# altair.net
KiCad netlist of a schematic drawn in EAGLE
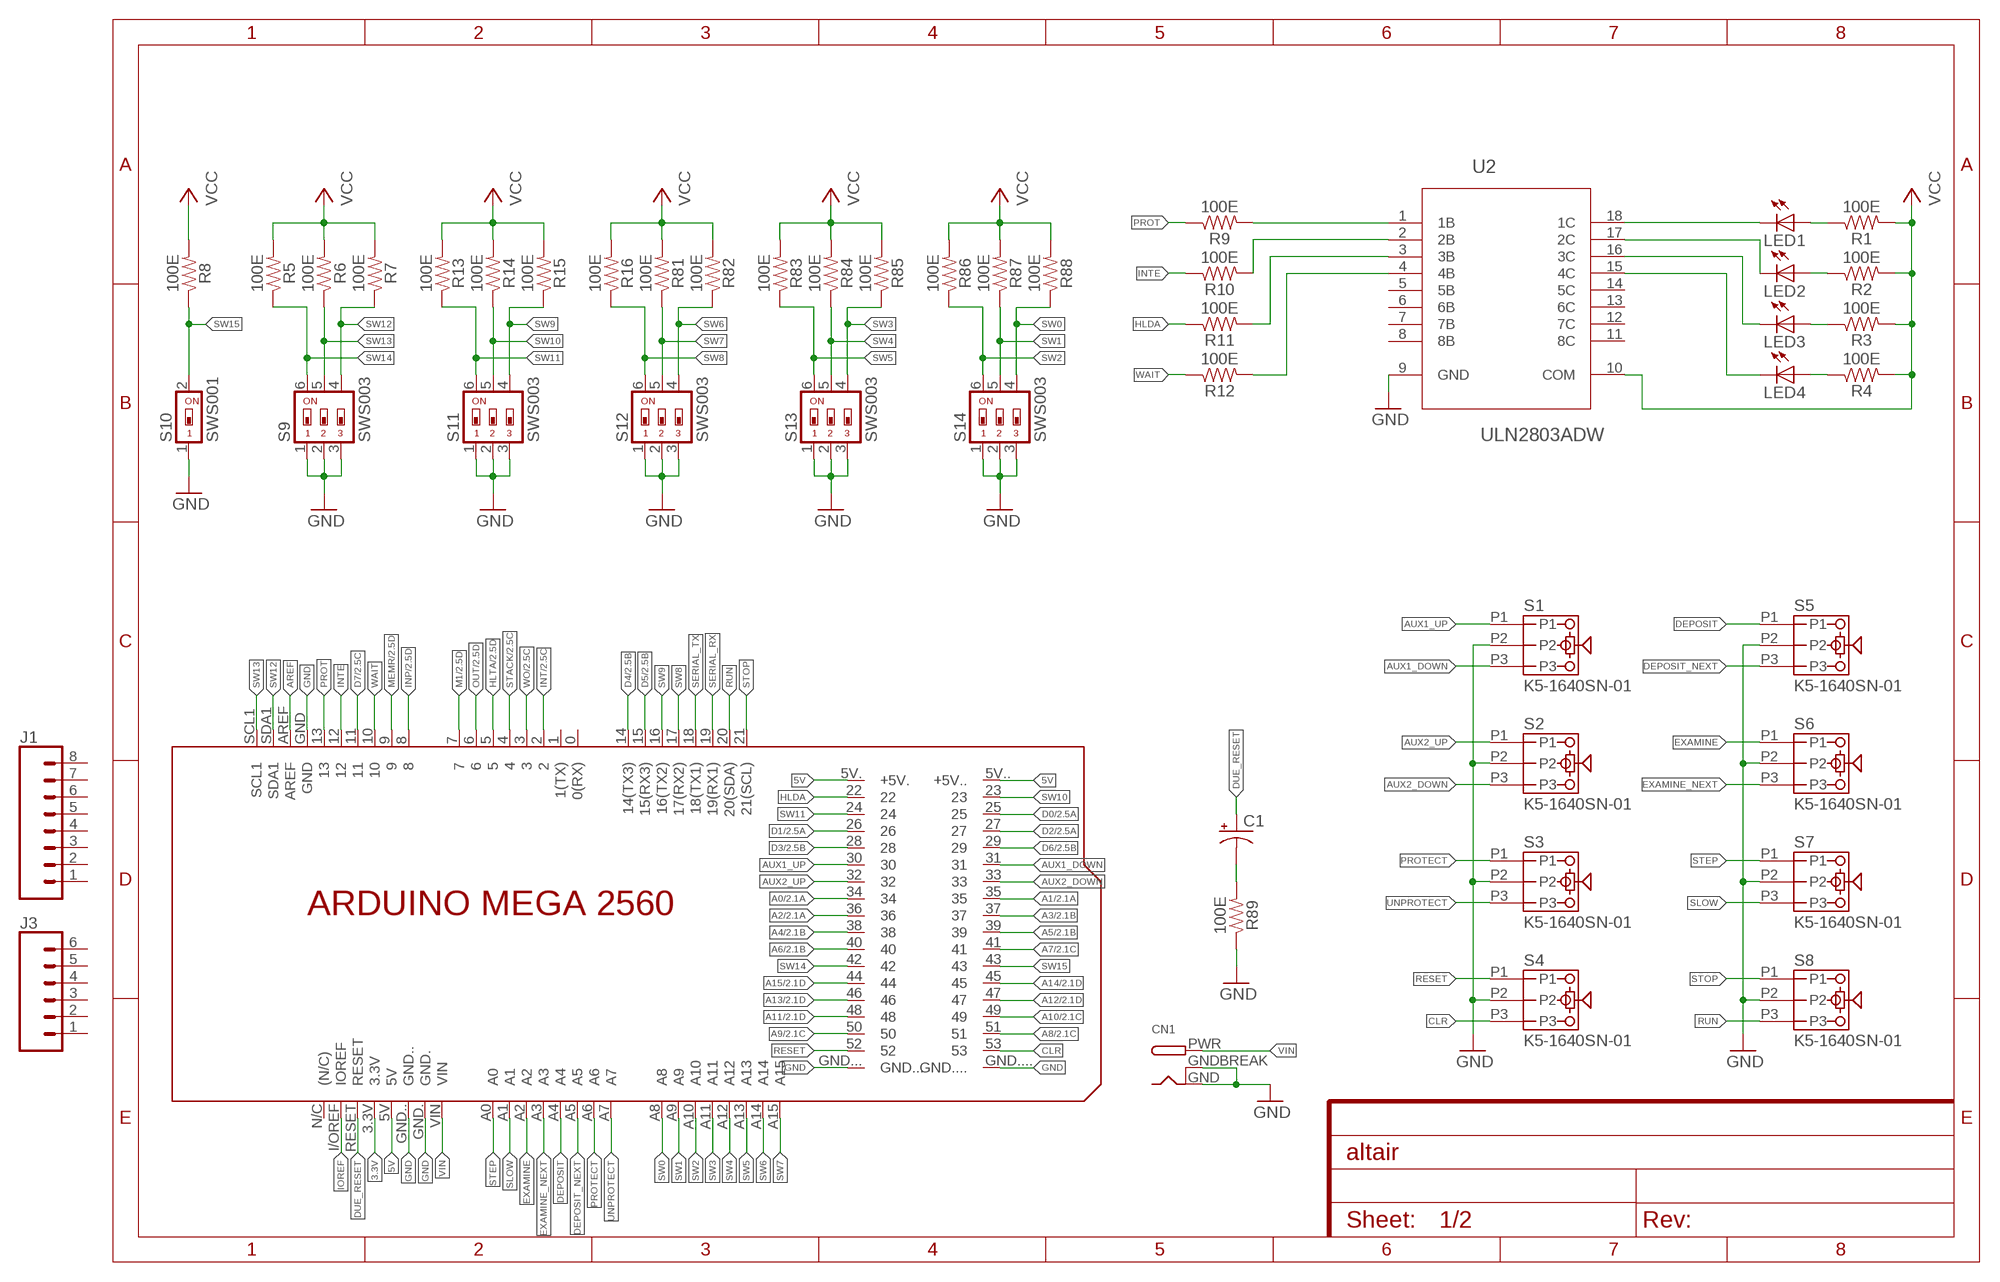
[diagram p0: schematic, sheet 1]
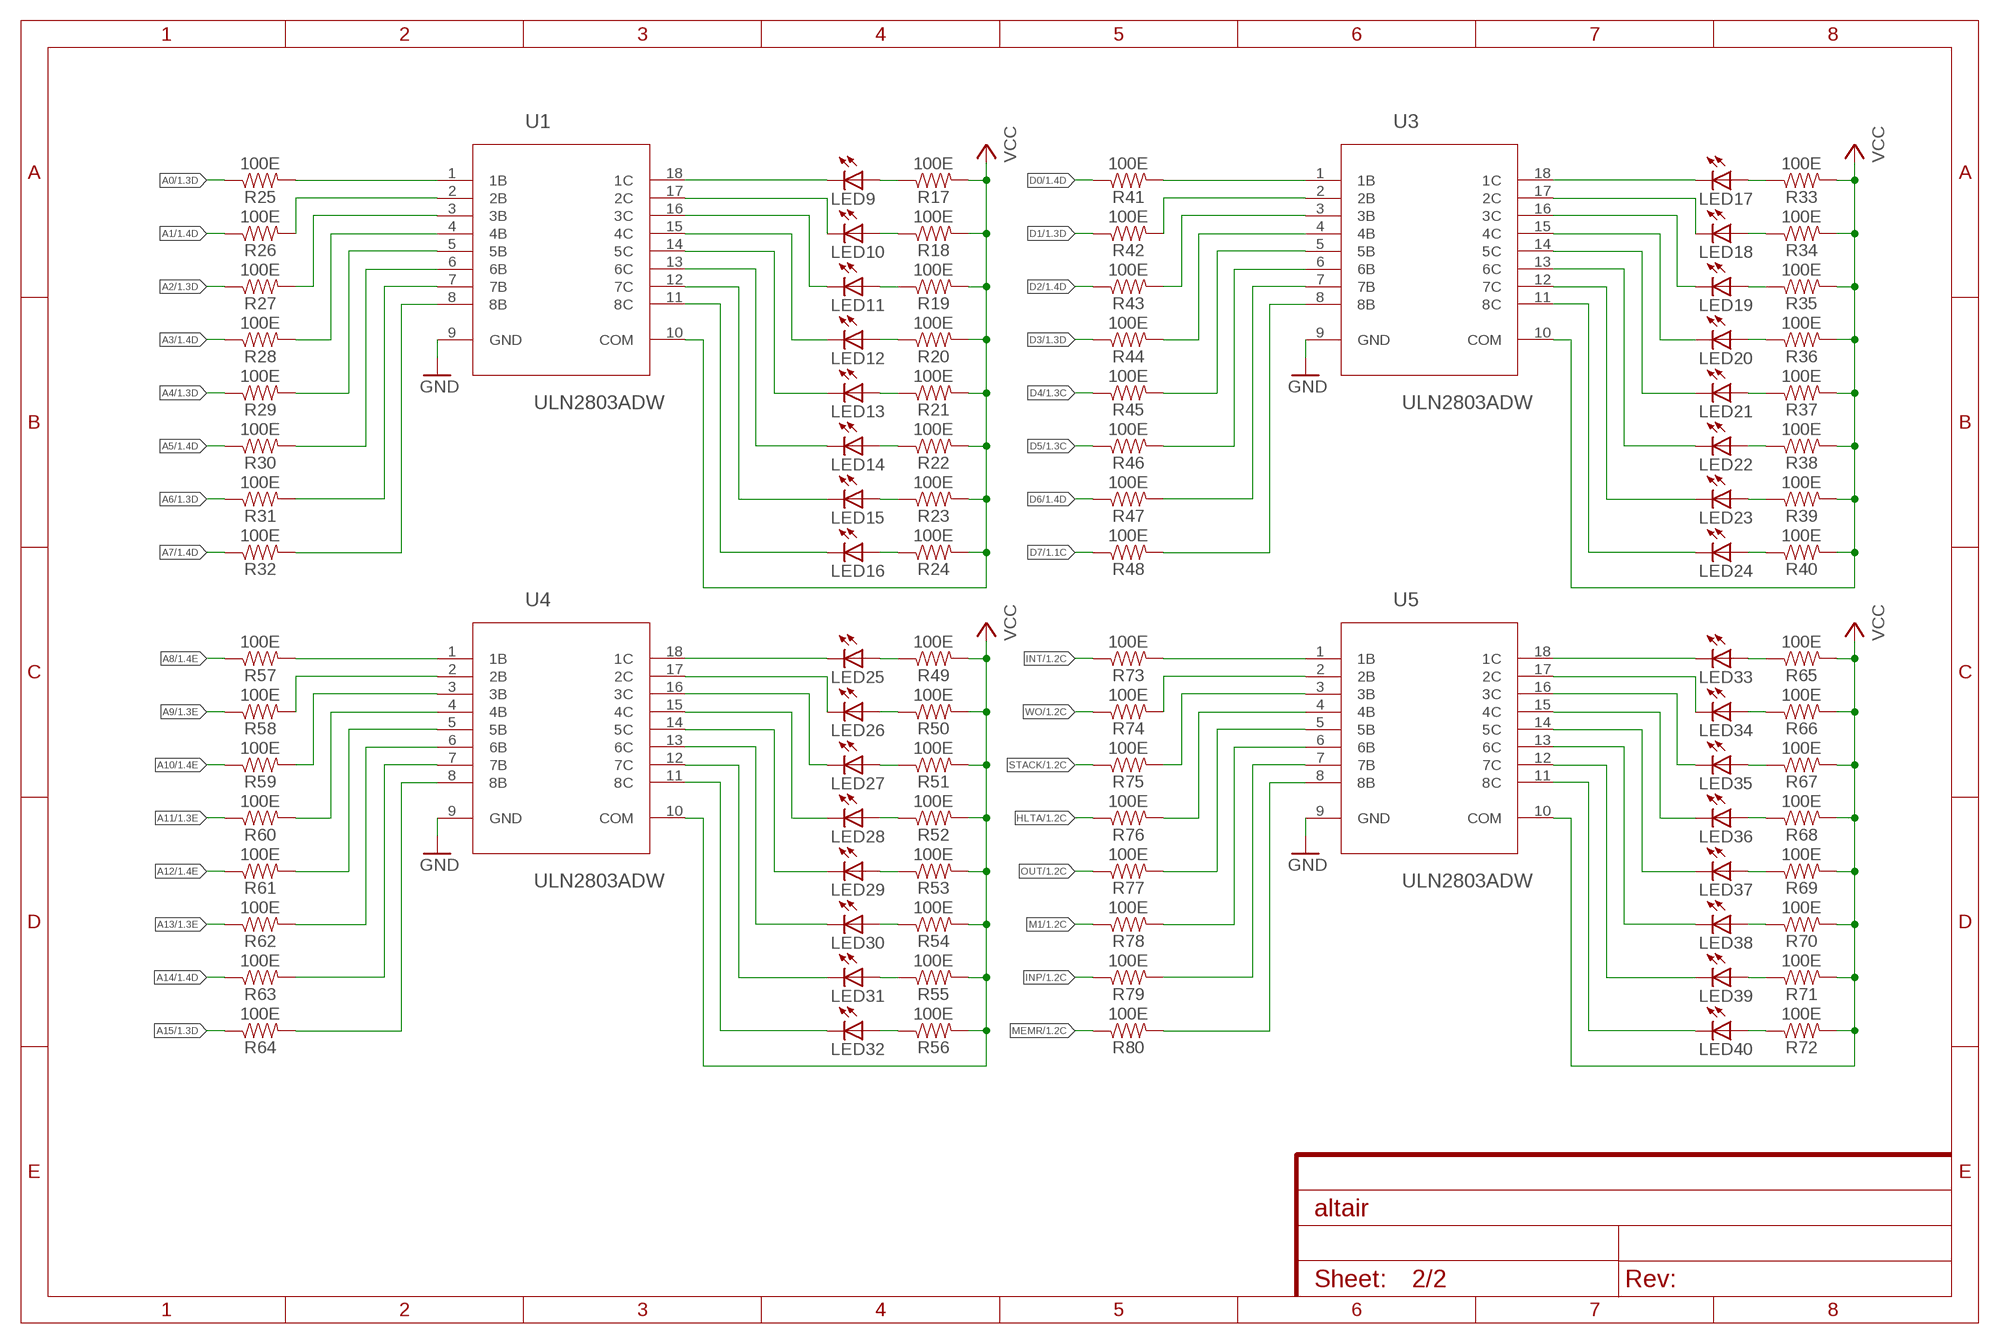
[diagram p1: schematic, sheet 2]

(export (version "E")
  (design (tool "Eeschema 10.0.6"))
  (components
    (comp (ref "C1")
      (value "CPOL-USD")
      (footprint "eagle-import:PANASONIC_D")
      (libsource (lib "eagle-import") (part "CPOL-USD"))
    )
    (comp (ref "CN1")
      (value "DCBARRELPTH")
      (footprint "eagle-import:DCJACK_2MM_PTH")
      (libsource (lib "eagle-import") (part "DCBARRELPTH"))
    )
    (comp (ref "J1")
      (value "CONN_08LOCK")
      (footprint "eagle-import:1X08_LOCK")
      (libsource (lib "eagle-import") (part "CONN_08LOCK"))
    )
    (comp (ref "J3")
      (value "CONN_06LOCK")
      (footprint "eagle-import:1X06_LOCK")
      (libsource (lib "eagle-import") (part "CONN_06LOCK"))
    )
    (comp (ref "LED1")
      (value "LEDCHIP-LED0805")
      (footprint "eagle-import:CHIP-LED0805")
      (libsource (lib "eagle-import") (part "LEDCHIP-LED0805"))
    )
    (comp (ref "LED2")
      (value "LEDCHIP-LED0805")
      (footprint "eagle-import:CHIP-LED0805")
      (libsource (lib "eagle-import") (part "LEDCHIP-LED0805"))
    )
    (comp (ref "LED3")
      (value "LEDCHIP-LED0805")
      (footprint "eagle-import:CHIP-LED0805")
      (libsource (lib "eagle-import") (part "LEDCHIP-LED0805"))
    )
    (comp (ref "LED4")
      (value "LEDCHIP-LED0805")
      (footprint "eagle-import:CHIP-LED0805")
      (libsource (lib "eagle-import") (part "LEDCHIP-LED0805"))
    )
    (comp (ref "PCB2")
      (value "ARDUINO_MEGA2560")
      (footprint "eagle-import:ARDUINO_MEGA2560")
      (libsource (lib "eagle-import") (part "ARDUINO_MEGA2560"))
    )
    (comp (ref "R1")
      (value "100E")
      (footprint "eagle-import:0805")
      (libsource (lib "eagle-import") (part "RESISTOR0805"))
    )
    (comp (ref "R2")
      (value "100E")
      (footprint "eagle-import:0805")
      (libsource (lib "eagle-import") (part "RESISTOR0805"))
    )
    (comp (ref "R3")
      (value "100E")
      (footprint "eagle-import:0805")
      (libsource (lib "eagle-import") (part "RESISTOR0805"))
    )
    (comp (ref "R4")
      (value "100E")
      (footprint "eagle-import:0805")
      (libsource (lib "eagle-import") (part "RESISTOR0805"))
    )
    (comp (ref "R5")
      (value "100E")
      (footprint "eagle-import:0805")
      (libsource (lib "eagle-import") (part "RESISTOR0805"))
    )
    (comp (ref "R6")
      (value "100E")
      (footprint "eagle-import:0805")
      (libsource (lib "eagle-import") (part "RESISTOR0805"))
    )
    (comp (ref "R7")
      (value "100E")
      (footprint "eagle-import:0805")
      (libsource (lib "eagle-import") (part "RESISTOR0805"))
    )
    (comp (ref "R8")
      (value "100E")
      (footprint "eagle-import:0805")
      (libsource (lib "eagle-import") (part "RESISTOR0805"))
    )
    (comp (ref "R9")
      (value "100E")
      (footprint "eagle-import:0805")
      (libsource (lib "eagle-import") (part "RESISTOR0805"))
    )
    (comp (ref "R10")
      (value "100E")
      (footprint "eagle-import:0805")
      (libsource (lib "eagle-import") (part "RESISTOR0805"))
    )
    (comp (ref "R11")
      (value "100E")
      (footprint "eagle-import:0805")
      (libsource (lib "eagle-import") (part "RESISTOR0805"))
    )
    (comp (ref "R12")
      (value "100E")
      (footprint "eagle-import:0805")
      (libsource (lib "eagle-import") (part "RESISTOR0805"))
    )
    (comp (ref "R13")
      (value "100E")
      (footprint "eagle-import:0805")
      (libsource (lib "eagle-import") (part "RESISTOR0805"))
    )
    (comp (ref "R14")
      (value "100E")
      (footprint "eagle-import:0805")
      (libsource (lib "eagle-import") (part "RESISTOR0805"))
    )
    (comp (ref "R15")
      (value "100E")
      (footprint "eagle-import:0805")
      (libsource (lib "eagle-import") (part "RESISTOR0805"))
    )
    (comp (ref "R16")
      (value "100E")
      (footprint "eagle-import:0805")
      (libsource (lib "eagle-import") (part "RESISTOR0805"))
    )
    (comp (ref "R81")
      (value "100E")
      (footprint "eagle-import:0805")
      (libsource (lib "eagle-import") (part "RESISTOR0805"))
    )
    (comp (ref "R82")
      (value "100E")
      (footprint "eagle-import:0805")
      (libsource (lib "eagle-import") (part "RESISTOR0805"))
    )
    (comp (ref "R83")
      (value "100E")
      (footprint "eagle-import:0805")
      (libsource (lib "eagle-import") (part "RESISTOR0805"))
    )
    (comp (ref "R84")
      (value "100E")
      (footprint "eagle-import:0805")
      (libsource (lib "eagle-import") (part "RESISTOR0805"))
    )
    (comp (ref "R85")
      (value "100E")
      (footprint "eagle-import:0805")
      (libsource (lib "eagle-import") (part "RESISTOR0805"))
    )
    (comp (ref "R86")
      (value "100E")
      (footprint "eagle-import:0805")
      (libsource (lib "eagle-import") (part "RESISTOR0805"))
    )
    (comp (ref "R87")
      (value "100E")
      (footprint "eagle-import:0805")
      (libsource (lib "eagle-import") (part "RESISTOR0805"))
    )
    (comp (ref "R88")
      (value "100E")
      (footprint "eagle-import:0805")
      (libsource (lib "eagle-import") (part "RESISTOR0805"))
    )
    (comp (ref "R89")
      (value "100E")
      (footprint "eagle-import:0805")
      (libsource (lib "eagle-import") (part "RESISTOR0805"))
    )
    (comp (ref "S1")
      (value "K5-1640SN-01")
      (footprint "eagle-import:K5-1640SN-01")
      (libsource (lib "eagle-import") (part "K5-1640SN-01"))
    )
    (comp (ref "S2")
      (value "K5-1640SN-01")
      (footprint "eagle-import:K5-1640SN-01")
      (libsource (lib "eagle-import") (part "K5-1640SN-01"))
    )
    (comp (ref "S3")
      (value "K5-1640SN-01")
      (footprint "eagle-import:K5-1640SN-01")
      (libsource (lib "eagle-import") (part "K5-1640SN-01"))
    )
    (comp (ref "S4")
      (value "K5-1640SN-01")
      (footprint "eagle-import:K5-1640SN-01")
      (libsource (lib "eagle-import") (part "K5-1640SN-01"))
    )
    (comp (ref "S5")
      (value "K5-1640SN-01")
      (footprint "eagle-import:K5-1640SN-01")
      (libsource (lib "eagle-import") (part "K5-1640SN-01"))
    )
    (comp (ref "S6")
      (value "K5-1640SN-01")
      (footprint "eagle-import:K5-1640SN-01")
      (libsource (lib "eagle-import") (part "K5-1640SN-01"))
    )
    (comp (ref "S7")
      (value "K5-1640SN-01")
      (footprint "eagle-import:K5-1640SN-01")
      (libsource (lib "eagle-import") (part "K5-1640SN-01"))
    )
    (comp (ref "S8")
      (value "K5-1640SN-01")
      (footprint "eagle-import:K5-1640SN-01")
      (libsource (lib "eagle-import") (part "K5-1640SN-01"))
    )
    (comp (ref "S9")
      (value "SWS003")
      (footprint "eagle-import:SMS-003")
      (libsource (lib "eagle-import") (part "SWS003"))
    )
    (comp (ref "S10")
      (value "SWS001")
      (footprint "eagle-import:SMS-001")
      (libsource (lib "eagle-import") (part "SWS001"))
    )
    (comp (ref "S11")
      (value "SWS003")
      (footprint "eagle-import:SMS-003")
      (libsource (lib "eagle-import") (part "SWS003"))
    )
    (comp (ref "S12")
      (value "SWS003")
      (footprint "eagle-import:SMS-003")
      (libsource (lib "eagle-import") (part "SWS003"))
    )
    (comp (ref "S13")
      (value "SWS003")
      (footprint "eagle-import:SMS-003")
      (libsource (lib "eagle-import") (part "SWS003"))
    )
    (comp (ref "S14")
      (value "SWS003")
      (footprint "eagle-import:SMS-003")
      (libsource (lib "eagle-import") (part "SWS003"))
    )
    (comp (ref "U2")
      (value "ULN2803ADW")
      (footprint "eagle-import:SOIC127P1030X265-18N")
      (libsource (lib "eagle-import") (part "ULN2803ADW"))
    )
    (comp (ref "LED9")
      (value "LEDCHIP-LED0805")
      (footprint "eagle-import:CHIP-LED0805")
      (libsource (lib "eagle-import") (part "LEDCHIP-LED0805"))
    )
    (comp (ref "LED10")
      (value "LEDCHIP-LED0805")
      (footprint "eagle-import:CHIP-LED0805")
      (libsource (lib "eagle-import") (part "LEDCHIP-LED0805"))
    )
    (comp (ref "LED11")
      (value "LEDCHIP-LED0805")
      (footprint "eagle-import:CHIP-LED0805")
      (libsource (lib "eagle-import") (part "LEDCHIP-LED0805"))
    )
    (comp (ref "LED12")
      (value "LEDCHIP-LED0805")
      (footprint "eagle-import:CHIP-LED0805")
      (libsource (lib "eagle-import") (part "LEDCHIP-LED0805"))
    )
    (comp (ref "LED13")
      (value "LEDCHIP-LED0805")
      (footprint "eagle-import:CHIP-LED0805")
      (libsource (lib "eagle-import") (part "LEDCHIP-LED0805"))
    )
    (comp (ref "LED14")
      (value "LEDCHIP-LED0805")
      (footprint "eagle-import:CHIP-LED0805")
      (libsource (lib "eagle-import") (part "LEDCHIP-LED0805"))
    )
    (comp (ref "LED15")
      (value "LEDCHIP-LED0805")
      (footprint "eagle-import:CHIP-LED0805")
      (libsource (lib "eagle-import") (part "LEDCHIP-LED0805"))
    )
    (comp (ref "LED16")
      (value "LEDCHIP-LED0805")
      (footprint "eagle-import:CHIP-LED0805")
      (libsource (lib "eagle-import") (part "LEDCHIP-LED0805"))
    )
    (comp (ref "LED17")
      (value "LEDCHIP-LED0805")
      (footprint "eagle-import:CHIP-LED0805")
      (libsource (lib "eagle-import") (part "LEDCHIP-LED0805"))
    )
    (comp (ref "LED18")
      (value "LEDCHIP-LED0805")
      (footprint "eagle-import:CHIP-LED0805")
      (libsource (lib "eagle-import") (part "LEDCHIP-LED0805"))
    )
    (comp (ref "LED19")
      (value "LEDCHIP-LED0805")
      (footprint "eagle-import:CHIP-LED0805")
      (libsource (lib "eagle-import") (part "LEDCHIP-LED0805"))
    )
    (comp (ref "LED20")
      (value "LEDCHIP-LED0805")
      (footprint "eagle-import:CHIP-LED0805")
      (libsource (lib "eagle-import") (part "LEDCHIP-LED0805"))
    )
    (comp (ref "LED21")
      (value "LEDCHIP-LED0805")
      (footprint "eagle-import:CHIP-LED0805")
      (libsource (lib "eagle-import") (part "LEDCHIP-LED0805"))
    )
    (comp (ref "LED22")
      (value "LEDCHIP-LED0805")
      (footprint "eagle-import:CHIP-LED0805")
      (libsource (lib "eagle-import") (part "LEDCHIP-LED0805"))
    )
    (comp (ref "LED23")
      (value "LEDCHIP-LED0805")
      (footprint "eagle-import:CHIP-LED0805")
      (libsource (lib "eagle-import") (part "LEDCHIP-LED0805"))
    )
    (comp (ref "LED24")
      (value "LEDCHIP-LED0805")
      (footprint "eagle-import:CHIP-LED0805")
      (libsource (lib "eagle-import") (part "LEDCHIP-LED0805"))
    )
    (comp (ref "LED25")
      (value "LEDCHIP-LED0805")
      (footprint "eagle-import:CHIP-LED0805")
      (libsource (lib "eagle-import") (part "LEDCHIP-LED0805"))
    )
    (comp (ref "LED26")
      (value "LEDCHIP-LED0805")
      (footprint "eagle-import:CHIP-LED0805")
      (libsource (lib "eagle-import") (part "LEDCHIP-LED0805"))
    )
    (comp (ref "LED27")
      (value "LEDCHIP-LED0805")
      (footprint "eagle-import:CHIP-LED0805")
      (libsource (lib "eagle-import") (part "LEDCHIP-LED0805"))
    )
    (comp (ref "LED28")
      (value "LEDCHIP-LED0805")
      (footprint "eagle-import:CHIP-LED0805")
      (libsource (lib "eagle-import") (part "LEDCHIP-LED0805"))
    )
    (comp (ref "LED29")
      (value "LEDCHIP-LED0805")
      (footprint "eagle-import:CHIP-LED0805")
      (libsource (lib "eagle-import") (part "LEDCHIP-LED0805"))
    )
    (comp (ref "LED30")
      (value "LEDCHIP-LED0805")
      (footprint "eagle-import:CHIP-LED0805")
      (libsource (lib "eagle-import") (part "LEDCHIP-LED0805"))
    )
    (comp (ref "LED31")
      (value "LEDCHIP-LED0805")
      (footprint "eagle-import:CHIP-LED0805")
      (libsource (lib "eagle-import") (part "LEDCHIP-LED0805"))
    )
    (comp (ref "LED32")
      (value "LEDCHIP-LED0805")
      (footprint "eagle-import:CHIP-LED0805")
      (libsource (lib "eagle-import") (part "LEDCHIP-LED0805"))
    )
    (comp (ref "LED33")
      (value "LEDCHIP-LED0805")
      (footprint "eagle-import:CHIP-LED0805")
      (libsource (lib "eagle-import") (part "LEDCHIP-LED0805"))
    )
    (comp (ref "LED34")
      (value "LEDCHIP-LED0805")
      (footprint "eagle-import:CHIP-LED0805")
      (libsource (lib "eagle-import") (part "LEDCHIP-LED0805"))
    )
    (comp (ref "LED35")
      (value "LEDCHIP-LED0805")
      (footprint "eagle-import:CHIP-LED0805")
      (libsource (lib "eagle-import") (part "LEDCHIP-LED0805"))
    )
    (comp (ref "LED36")
      (value "LEDCHIP-LED0805")
      (footprint "eagle-import:CHIP-LED0805")
      (libsource (lib "eagle-import") (part "LEDCHIP-LED0805"))
    )
    (comp (ref "LED37")
      (value "LEDCHIP-LED0805")
      (footprint "eagle-import:CHIP-LED0805")
      (libsource (lib "eagle-import") (part "LEDCHIP-LED0805"))
    )
    (comp (ref "LED38")
      (value "LEDCHIP-LED0805")
      (footprint "eagle-import:CHIP-LED0805")
      (libsource (lib "eagle-import") (part "LEDCHIP-LED0805"))
    )
    (comp (ref "LED39")
      (value "LEDCHIP-LED0805")
      (footprint "eagle-import:CHIP-LED0805")
      (libsource (lib "eagle-import") (part "LEDCHIP-LED0805"))
    )
    (comp (ref "LED40")
      (value "LEDCHIP-LED0805")
      (footprint "eagle-import:CHIP-LED0805")
      (libsource (lib "eagle-import") (part "LEDCHIP-LED0805"))
    )
    (comp (ref "R17")
      (value "100E")
      (footprint "eagle-import:0805")
      (libsource (lib "eagle-import") (part "RESISTOR0805"))
    )
    (comp (ref "R18")
      (value "100E")
      (footprint "eagle-import:0805")
      (libsource (lib "eagle-import") (part "RESISTOR0805"))
    )
    (comp (ref "R19")
      (value "100E")
      (footprint "eagle-import:0805")
      (libsource (lib "eagle-import") (part "RESISTOR0805"))
    )
    (comp (ref "R20")
      (value "100E")
      (footprint "eagle-import:0805")
      (libsource (lib "eagle-import") (part "RESISTOR0805"))
    )
    (comp (ref "R21")
      (value "100E")
      (footprint "eagle-import:0805")
      (libsource (lib "eagle-import") (part "RESISTOR0805"))
    )
    (comp (ref "R22")
      (value "100E")
      (footprint "eagle-import:0805")
      (libsource (lib "eagle-import") (part "RESISTOR0805"))
    )
    (comp (ref "R23")
      (value "100E")
      (footprint "eagle-import:0805")
      (libsource (lib "eagle-import") (part "RESISTOR0805"))
    )
    (comp (ref "R24")
      (value "100E")
      (footprint "eagle-import:0805")
      (libsource (lib "eagle-import") (part "RESISTOR0805"))
    )
    (comp (ref "R25")
      (value "100E")
      (footprint "eagle-import:0805")
      (libsource (lib "eagle-import") (part "RESISTOR0805"))
    )
    (comp (ref "R26")
      (value "100E")
      (footprint "eagle-import:0805")
      (libsource (lib "eagle-import") (part "RESISTOR0805"))
    )
    (comp (ref "R27")
      (value "100E")
      (footprint "eagle-import:0805")
      (libsource (lib "eagle-import") (part "RESISTOR0805"))
    )
    (comp (ref "R28")
      (value "100E")
      (footprint "eagle-import:0805")
      (libsource (lib "eagle-import") (part "RESISTOR0805"))
    )
    (comp (ref "R29")
      (value "100E")
      (footprint "eagle-import:0805")
      (libsource (lib "eagle-import") (part "RESISTOR0805"))
    )
    (comp (ref "R30")
      (value "100E")
      (footprint "eagle-import:0805")
      (libsource (lib "eagle-import") (part "RESISTOR0805"))
    )
    (comp (ref "R31")
      (value "100E")
      (footprint "eagle-import:0805")
      (libsource (lib "eagle-import") (part "RESISTOR0805"))
    )
    (comp (ref "R32")
      (value "100E")
      (footprint "eagle-import:0805")
      (libsource (lib "eagle-import") (part "RESISTOR0805"))
    )
    (comp (ref "R33")
      (value "100E")
      (footprint "eagle-import:0805")
      (libsource (lib "eagle-import") (part "RESISTOR0805"))
    )
    (comp (ref "R34")
      (value "100E")
      (footprint "eagle-import:0805")
      (libsource (lib "eagle-import") (part "RESISTOR0805"))
    )
    (comp (ref "R35")
      (value "100E")
      (footprint "eagle-import:0805")
      (libsource (lib "eagle-import") (part "RESISTOR0805"))
    )
    (comp (ref "R36")
      (value "100E")
      (footprint "eagle-import:0805")
      (libsource (lib "eagle-import") (part "RESISTOR0805"))
    )
    (comp (ref "R37")
      (value "100E")
      (footprint "eagle-import:0805")
      (libsource (lib "eagle-import") (part "RESISTOR0805"))
    )
    (comp (ref "R38")
      (value "100E")
      (footprint "eagle-import:0805")
      (libsource (lib "eagle-import") (part "RESISTOR0805"))
    )
    (comp (ref "R39")
      (value "100E")
      (footprint "eagle-import:0805")
      (libsource (lib "eagle-import") (part "RESISTOR0805"))
    )
    (comp (ref "R40")
      (value "100E")
      (footprint "eagle-import:0805")
      (libsource (lib "eagle-import") (part "RESISTOR0805"))
    )
    (comp (ref "R41")
      (value "100E")
      (footprint "eagle-import:0805")
      (libsource (lib "eagle-import") (part "RESISTOR0805"))
    )
    (comp (ref "R42")
      (value "100E")
      (footprint "eagle-import:0805")
      (libsource (lib "eagle-import") (part "RESISTOR0805"))
    )
    (comp (ref "R43")
      (value "100E")
      (footprint "eagle-import:0805")
      (libsource (lib "eagle-import") (part "RESISTOR0805"))
    )
    (comp (ref "R44")
      (value "100E")
      (footprint "eagle-import:0805")
      (libsource (lib "eagle-import") (part "RESISTOR0805"))
    )
    (comp (ref "R45")
      (value "100E")
      (footprint "eagle-import:0805")
      (libsource (lib "eagle-import") (part "RESISTOR0805"))
    )
    (comp (ref "R46")
      (value "100E")
      (footprint "eagle-import:0805")
      (libsource (lib "eagle-import") (part "RESISTOR0805"))
    )
    (comp (ref "R47")
      (value "100E")
      (footprint "eagle-import:0805")
      (libsource (lib "eagle-import") (part "RESISTOR0805"))
    )
    (comp (ref "R48")
      (value "100E")
      (footprint "eagle-import:0805")
      (libsource (lib "eagle-import") (part "RESISTOR0805"))
    )
    (comp (ref "R49")
      (value "100E")
      (footprint "eagle-import:0805")
      (libsource (lib "eagle-import") (part "RESISTOR0805"))
    )
    (comp (ref "R50")
      (value "100E")
      (footprint "eagle-import:0805")
      (libsource (lib "eagle-import") (part "RESISTOR0805"))
    )
    (comp (ref "R51")
      (value "100E")
      (footprint "eagle-import:0805")
      (libsource (lib "eagle-import") (part "RESISTOR0805"))
    )
    (comp (ref "R52")
      (value "100E")
      (footprint "eagle-import:0805")
      (libsource (lib "eagle-import") (part "RESISTOR0805"))
    )
    (comp (ref "R53")
      (value "100E")
      (footprint "eagle-import:0805")
      (libsource (lib "eagle-import") (part "RESISTOR0805"))
    )
    (comp (ref "R54")
      (value "100E")
      (footprint "eagle-import:0805")
      (libsource (lib "eagle-import") (part "RESISTOR0805"))
    )
    (comp (ref "R55")
      (value "100E")
      (footprint "eagle-import:0805")
      (libsource (lib "eagle-import") (part "RESISTOR0805"))
    )
    (comp (ref "R56")
      (value "100E")
      (footprint "eagle-import:0805")
      (libsource (lib "eagle-import") (part "RESISTOR0805"))
    )
    (comp (ref "R57")
      (value "100E")
      (footprint "eagle-import:0805")
      (libsource (lib "eagle-import") (part "RESISTOR0805"))
    )
    (comp (ref "R58")
      (value "100E")
      (footprint "eagle-import:0805")
      (libsource (lib "eagle-import") (part "RESISTOR0805"))
    )
    (comp (ref "R59")
      (value "100E")
      (footprint "eagle-import:0805")
      (libsource (lib "eagle-import") (part "RESISTOR0805"))
    )
    (comp (ref "R60")
      (value "100E")
      (footprint "eagle-import:0805")
      (libsource (lib "eagle-import") (part "RESISTOR0805"))
    )
    (comp (ref "R61")
      (value "100E")
      (footprint "eagle-import:0805")
      (libsource (lib "eagle-import") (part "RESISTOR0805"))
    )
    (comp (ref "R62")
      (value "100E")
      (footprint "eagle-import:0805")
      (libsource (lib "eagle-import") (part "RESISTOR0805"))
    )
    (comp (ref "R63")
      (value "100E")
      (footprint "eagle-import:0805")
      (libsource (lib "eagle-import") (part "RESISTOR0805"))
    )
    (comp (ref "R64")
      (value "100E")
      (footprint "eagle-import:0805")
      (libsource (lib "eagle-import") (part "RESISTOR0805"))
    )
    (comp (ref "R65")
      (value "100E")
      (footprint "eagle-import:0805")
      (libsource (lib "eagle-import") (part "RESISTOR0805"))
    )
    (comp (ref "R66")
      (value "100E")
      (footprint "eagle-import:0805")
      (libsource (lib "eagle-import") (part "RESISTOR0805"))
    )
    (comp (ref "R67")
      (value "100E")
      (footprint "eagle-import:0805")
      (libsource (lib "eagle-import") (part "RESISTOR0805"))
    )
    (comp (ref "R68")
      (value "100E")
      (footprint "eagle-import:0805")
      (libsource (lib "eagle-import") (part "RESISTOR0805"))
    )
    (comp (ref "R69")
      (value "100E")
      (footprint "eagle-import:0805")
      (libsource (lib "eagle-import") (part "RESISTOR0805"))
    )
    (comp (ref "R70")
      (value "100E")
      (footprint "eagle-import:0805")
      (libsource (lib "eagle-import") (part "RESISTOR0805"))
    )
    (comp (ref "R71")
      (value "100E")
      (footprint "eagle-import:0805")
      (libsource (lib "eagle-import") (part "RESISTOR0805"))
    )
    (comp (ref "R72")
      (value "100E")
      (footprint "eagle-import:0805")
      (libsource (lib "eagle-import") (part "RESISTOR0805"))
    )
    (comp (ref "R73")
      (value "100E")
      (footprint "eagle-import:0805")
      (libsource (lib "eagle-import") (part "RESISTOR0805"))
    )
    (comp (ref "R74")
      (value "100E")
      (footprint "eagle-import:0805")
      (libsource (lib "eagle-import") (part "RESISTOR0805"))
    )
    (comp (ref "R75")
      (value "100E")
      (footprint "eagle-import:0805")
      (libsource (lib "eagle-import") (part "RESISTOR0805"))
    )
    (comp (ref "R76")
      (value "100E")
      (footprint "eagle-import:0805")
      (libsource (lib "eagle-import") (part "RESISTOR0805"))
    )
    (comp (ref "R77")
      (value "100E")
      (footprint "eagle-import:0805")
      (libsource (lib "eagle-import") (part "RESISTOR0805"))
    )
    (comp (ref "R78")
      (value "100E")
      (footprint "eagle-import:0805")
      (libsource (lib "eagle-import") (part "RESISTOR0805"))
    )
    (comp (ref "R79")
      (value "100E")
      (footprint "eagle-import:0805")
      (libsource (lib "eagle-import") (part "RESISTOR0805"))
    )
    (comp (ref "R80")
      (value "100E")
      (footprint "eagle-import:0805")
      (libsource (lib "eagle-import") (part "RESISTOR0805"))
    )
    (comp (ref "U1")
      (value "ULN2803ADW")
      (footprint "eagle-import:SOIC127P1030X265-18N")
      (libsource (lib "eagle-import") (part "ULN2803ADW"))
    )
    (comp (ref "U3")
      (value "ULN2803ADW")
      (footprint "eagle-import:SOIC127P1030X265-18N")
      (libsource (lib "eagle-import") (part "ULN2803ADW"))
    )
    (comp (ref "U4")
      (value "ULN2803ADW")
      (footprint "eagle-import:SOIC127P1030X265-18N")
      (libsource (lib "eagle-import") (part "ULN2803ADW"))
    )
    (comp (ref "U5")
      (value "ULN2803ADW")
      (footprint "eagle-import:SOIC127P1030X265-18N")
      (libsource (lib "eagle-import") (part "ULN2803ADW"))
    )
  )
  (nets
    (net (code "1") (name "3.3V") (class "Default")
      (node (ref "PCB2") (pin "3.3V") (pinfunction "3.3V_3.3V") (pintype "bidirectional"))
    )
    (net (code "2") (name "5V") (class "Default")
      (node (ref "PCB2") (pin "5V") (pinfunction "5V_5V") (pintype "bidirectional"))
      (node (ref "PCB2") (pin "5V.") (pinfunction "+5V._5V.") (pintype "bidirectional"))
      (node (ref "PCB2") (pin "5V..") (pinfunction "+5V.._5V..") (pintype "bidirectional"))
    )
    (net (code "3") (name "A0") (class "Default")
      (node (ref "PCB2") (pin "34") (pinfunction "34_34") (pintype "bidirectional"))
      (node (ref "R25") (pin "1") (pinfunction "1_1") (pintype "passive"))
    )
    (net (code "4") (name "A1") (class "Default")
      (node (ref "PCB2") (pin "35") (pinfunction "35_35") (pintype "bidirectional"))
      (node (ref "R26") (pin "1") (pinfunction "1_1") (pintype "passive"))
    )
    (net (code "5") (name "A2") (class "Default")
      (node (ref "PCB2") (pin "36") (pinfunction "36_36") (pintype "bidirectional"))
      (node (ref "R27") (pin "1") (pinfunction "1_1") (pintype "passive"))
    )
    (net (code "6") (name "A3") (class "Default")
      (node (ref "PCB2") (pin "37") (pinfunction "37_37") (pintype "bidirectional"))
      (node (ref "R28") (pin "1") (pinfunction "1_1") (pintype "passive"))
    )
    (net (code "7") (name "A4") (class "Default")
      (node (ref "PCB2") (pin "38") (pinfunction "38_38") (pintype "bidirectional"))
      (node (ref "R29") (pin "1") (pinfunction "1_1") (pintype "passive"))
    )
    (net (code "8") (name "A5") (class "Default")
      (node (ref "PCB2") (pin "39") (pinfunction "39_39") (pintype "bidirectional"))
      (node (ref "R30") (pin "1") (pinfunction "1_1") (pintype "passive"))
    )
    (net (code "9") (name "A6") (class "Default")
      (node (ref "PCB2") (pin "40") (pinfunction "40_40") (pintype "bidirectional"))
      (node (ref "R31") (pin "1") (pinfunction "1_1") (pintype "passive"))
    )
    (net (code "10") (name "A7") (class "Default")
      (node (ref "PCB2") (pin "41") (pinfunction "41_41") (pintype "bidirectional"))
      (node (ref "R32") (pin "1") (pinfunction "1_1") (pintype "passive"))
    )
    (net (code "11") (name "A8") (class "Default")
      (node (ref "PCB2") (pin "51") (pinfunction "51_51") (pintype "bidirectional"))
      (node (ref "R57") (pin "1") (pinfunction "1_1") (pintype "passive"))
    )
    (net (code "12") (name "A9") (class "Default")
      (node (ref "PCB2") (pin "50") (pinfunction "50_50") (pintype "bidirectional"))
      (node (ref "R58") (pin "1") (pinfunction "1_1") (pintype "passive"))
    )
    (net (code "13") (name "A10") (class "Default")
      (node (ref "PCB2") (pin "49") (pinfunction "49_49") (pintype "bidirectional"))
      (node (ref "R59") (pin "1") (pinfunction "1_1") (pintype "passive"))
    )
    (net (code "14") (name "A11") (class "Default")
      (node (ref "PCB2") (pin "48") (pinfunction "48_48") (pintype "bidirectional"))
      (node (ref "R60") (pin "1") (pinfunction "1_1") (pintype "passive"))
    )
    (net (code "15") (name "A12") (class "Default")
      (node (ref "PCB2") (pin "47") (pinfunction "47_47") (pintype "bidirectional"))
      (node (ref "R61") (pin "1") (pinfunction "1_1") (pintype "passive"))
    )
    (net (code "16") (name "A13") (class "Default")
      (node (ref "PCB2") (pin "46") (pinfunction "46_46") (pintype "bidirectional"))
      (node (ref "R62") (pin "1") (pinfunction "1_1") (pintype "passive"))
    )
    (net (code "17") (name "A14") (class "Default")
      (node (ref "PCB2") (pin "45") (pinfunction "45_45") (pintype "bidirectional"))
      (node (ref "R63") (pin "1") (pinfunction "1_1") (pintype "passive"))
    )
    (net (code "18") (name "A15") (class "Default")
      (node (ref "PCB2") (pin "44") (pinfunction "44_44") (pintype "bidirectional"))
      (node (ref "R64") (pin "1") (pinfunction "1_1") (pintype "passive"))
    )
    (net (code "19") (name "AREF") (class "Default")
      (node (ref "PCB2") (pin "AREF") (pinfunction "AREF_AREF") (pintype "bidirectional"))
    )
    (net (code "20") (name "AUX1_DOWN") (class "Default")
      (node (ref "PCB2") (pin "31") (pinfunction "31_31") (pintype "bidirectional"))
      (node (ref "S1") (pin "P3") (pinfunction "P3_P3") (pintype "bidirectional"))
    )
    (net (code "21") (name "AUX1_UP") (class "Default")
      (node (ref "PCB2") (pin "30") (pinfunction "30_30") (pintype "bidirectional"))
      (node (ref "S1") (pin "P1") (pinfunction "P1_P1") (pintype "bidirectional"))
    )
    (net (code "22") (name "AUX2_DOWN") (class "Default")
      (node (ref "PCB2") (pin "33") (pinfunction "33_33") (pintype "bidirectional"))
      (node (ref "S2") (pin "P3") (pinfunction "P3_P3") (pintype "bidirectional"))
    )
    (net (code "23") (name "AUX2_UP") (class "Default")
      (node (ref "PCB2") (pin "32") (pinfunction "32_32") (pintype "bidirectional"))
      (node (ref "S2") (pin "P1") (pinfunction "P1_P1") (pintype "bidirectional"))
    )
    (net (code "24") (name "CLR") (class "Default")
      (node (ref "PCB2") (pin "53") (pinfunction "53_53") (pintype "bidirectional"))
      (node (ref "S4") (pin "P3") (pinfunction "P3_P3") (pintype "bidirectional"))
    )
    (net (code "25") (name "D0") (class "Default")
      (node (ref "PCB2") (pin "25") (pinfunction "25_25") (pintype "bidirectional"))
      (node (ref "R41") (pin "1") (pinfunction "1_1") (pintype "passive"))
    )
    (net (code "26") (name "D1") (class "Default")
      (node (ref "PCB2") (pin "26") (pinfunction "26_26") (pintype "bidirectional"))
      (node (ref "R42") (pin "1") (pinfunction "1_1") (pintype "passive"))
    )
    (net (code "27") (name "D2") (class "Default")
      (node (ref "PCB2") (pin "27") (pinfunction "27_27") (pintype "bidirectional"))
      (node (ref "R43") (pin "1") (pinfunction "1_1") (pintype "passive"))
    )
    (net (code "28") (name "D3") (class "Default")
      (node (ref "PCB2") (pin "28") (pinfunction "28_28") (pintype "bidirectional"))
      (node (ref "R44") (pin "1") (pinfunction "1_1") (pintype "passive"))
    )
    (net (code "29") (name "D4") (class "Default")
      (node (ref "PCB2") (pin "14") (pinfunction "14(TX3)_14") (pintype "bidirectional"))
      (node (ref "R45") (pin "1") (pinfunction "1_1") (pintype "passive"))
    )
    (net (code "30") (name "D5") (class "Default")
      (node (ref "PCB2") (pin "15") (pinfunction "15(RX3)_15") (pintype "bidirectional"))
      (node (ref "R46") (pin "1") (pinfunction "1_1") (pintype "passive"))
    )
    (net (code "31") (name "D6") (class "Default")
      (node (ref "PCB2") (pin "29") (pinfunction "29_29") (pintype "bidirectional"))
      (node (ref "R47") (pin "1") (pinfunction "1_1") (pintype "passive"))
    )
    (net (code "32") (name "D7") (class "Default")
      (node (ref "PCB2") (pin "11") (pinfunction "11_11") (pintype "bidirectional"))
      (node (ref "R48") (pin "1") (pinfunction "1_1") (pintype "passive"))
    )
    (net (code "33") (name "DEPOSIT") (class "Default")
      (node (ref "PCB2") (pin "A4") (pinfunction "A4_A4") (pintype "bidirectional"))
      (node (ref "S5") (pin "P1") (pinfunction "P1_P1") (pintype "bidirectional"))
    )
    (net (code "34") (name "DEPOSIT_NEXT") (class "Default")
      (node (ref "PCB2") (pin "A5") (pinfunction "A5_A5") (pintype "bidirectional"))
      (node (ref "S5") (pin "P3") (pinfunction "P3_P3") (pintype "bidirectional"))
    )
    (net (code "35") (name "DUE_RESET") (class "Default")
      (node (ref "C1") (pin "+") (pinfunction "+_+") (pintype "passive"))
      (node (ref "PCB2") (pin "RESET") (pinfunction "RESET_RESET") (pintype "bidirectional"))
    )
    (net (code "36") (name "EXAMINE") (class "Default")
      (node (ref "PCB2") (pin "A2") (pinfunction "A2_A2") (pintype "bidirectional"))
      (node (ref "S6") (pin "P1") (pinfunction "P1_P1") (pintype "bidirectional"))
    )
    (net (code "37") (name "EXAMINE_NEXT") (class "Default")
      (node (ref "PCB2") (pin "A3") (pinfunction "A3_A3") (pintype "bidirectional"))
      (node (ref "S6") (pin "P3") (pinfunction "P3_P3") (pintype "bidirectional"))
    )
    (net (code "38") (name "GND") (class "Default")
      (node (ref "CN1") (pin "GND") (pinfunction "GND_GND") (pintype "power_in"))
      (node (ref "CN1") (pin "GNDBREAK") (pinfunction "GNDBREAK_GNDBREAK") (pintype "power_in"))
      (node (ref "PCB2") (pin "GND") (pinfunction "GND_GND") (pintype "bidirectional"))
      (node (ref "PCB2") (pin "GND.") (pinfunction "GND._GND.") (pintype "bidirectional"))
      (node (ref "PCB2") (pin "GND..") (pinfunction "GND.._GND..") (pintype "bidirectional"))
      (node (ref "PCB2") (pin "GND...") (pinfunction "GND..._GND...") (pintype "bidirectional"))
      (node (ref "PCB2") (pin "GND....") (pinfunction "GND...._GND....") (pintype "bidirectional"))
      (node (ref "R89") (pin "1") (pinfunction "1_1") (pintype "passive"))
      (node (ref "S1") (pin "P2") (pinfunction "P2_P2") (pintype "bidirectional"))
      (node (ref "S10") (pin "1") (pinfunction "1_1") (pintype "passive"))
      (node (ref "S11") (pin "1") (pinfunction "1_1") (pintype "passive"))
      (node (ref "S11") (pin "2") (pinfunction "2_2") (pintype "passive"))
      (node (ref "S11") (pin "3") (pinfunction "3_3") (pintype "passive"))
      (node (ref "S12") (pin "1") (pinfunction "1_1") (pintype "passive"))
      (node (ref "S12") (pin "2") (pinfunction "2_2") (pintype "passive"))
      (node (ref "S12") (pin "3") (pinfunction "3_3") (pintype "passive"))
      (node (ref "S13") (pin "1") (pinfunction "1_1") (pintype "passive"))
      (node (ref "S13") (pin "2") (pinfunction "2_2") (pintype "passive"))
      (node (ref "S13") (pin "3") (pinfunction "3_3") (pintype "passive"))
      (node (ref "S14") (pin "1") (pinfunction "1_1") (pintype "passive"))
      (node (ref "S14") (pin "2") (pinfunction "2_2") (pintype "passive"))
      (node (ref "S14") (pin "3") (pinfunction "3_3") (pintype "passive"))
      (node (ref "S2") (pin "P2") (pinfunction "P2_P2") (pintype "bidirectional"))
      (node (ref "S3") (pin "P2") (pinfunction "P2_P2") (pintype "bidirectional"))
      (node (ref "S4") (pin "P2") (pinfunction "P2_P2") (pintype "bidirectional"))
      (node (ref "S5") (pin "P2") (pinfunction "P2_P2") (pintype "bidirectional"))
      (node (ref "S6") (pin "P2") (pinfunction "P2_P2") (pintype "bidirectional"))
      (node (ref "S7") (pin "P2") (pinfunction "P2_P2") (pintype "bidirectional"))
      (node (ref "S8") (pin "P2") (pinfunction "P2_P2") (pintype "bidirectional"))
      (node (ref "S9") (pin "1") (pinfunction "1_1") (pintype "passive"))
      (node (ref "S9") (pin "2") (pinfunction "2_2") (pintype "passive"))
      (node (ref "S9") (pin "3") (pinfunction "3_3") (pintype "passive"))
      (node (ref "U1") (pin "9") (pinfunction "GND_9") (pintype "passive"))
      (node (ref "U2") (pin "9") (pinfunction "GND_9") (pintype "passive"))
      (node (ref "U3") (pin "9") (pinfunction "GND_9") (pintype "passive"))
      (node (ref "U4") (pin "9") (pinfunction "GND_9") (pintype "passive"))
      (node (ref "U5") (pin "9") (pinfunction "GND_9") (pintype "passive"))
    )
    (net (code "39") (name "HLDA") (class "Default")
      (node (ref "PCB2") (pin "22") (pinfunction "22_22") (pintype "bidirectional"))
      (node (ref "R11") (pin "1") (pinfunction "1_1") (pintype "passive"))
    )
    (net (code "40") (name "HLTA") (class "Default")
      (node (ref "PCB2") (pin "5") (pinfunction "5_5") (pintype "bidirectional"))
      (node (ref "R76") (pin "1") (pinfunction "1_1") (pintype "passive"))
    )
    (net (code "41") (name "INP") (class "Default")
      (node (ref "PCB2") (pin "8") (pinfunction "8_8") (pintype "bidirectional"))
      (node (ref "R79") (pin "1") (pinfunction "1_1") (pintype "passive"))
    )
    (net (code "42") (name "INT") (class "Default")
      (node (ref "PCB2") (pin "2") (pinfunction "2_2") (pintype "bidirectional"))
      (node (ref "R73") (pin "1") (pinfunction "1_1") (pintype "passive"))
    )
    (net (code "43") (name "INTE") (class "Default")
      (node (ref "PCB2") (pin "12") (pinfunction "12_12") (pintype "bidirectional"))
      (node (ref "R10") (pin "1") (pinfunction "1_1") (pintype "passive"))
    )
    (net (code "44") (name "IOREF") (class "Default")
      (node (ref "PCB2") (pin "I/OREF") (pinfunction "IOREF_I/OREF") (pintype "bidirectional"))
    )
    (net (code "45") (name "M1") (class "Default")
      (node (ref "PCB2") (pin "7") (pinfunction "7_7") (pintype "bidirectional"))
      (node (ref "R78") (pin "1") (pinfunction "1_1") (pintype "passive"))
    )
    (net (code "46") (name "MEMR") (class "Default")
      (node (ref "PCB2") (pin "9") (pinfunction "9_9") (pintype "bidirectional"))
      (node (ref "R80") (pin "1") (pinfunction "1_1") (pintype "passive"))
    )
    (net (code "47") (name "Net-(C1-Pad-)") (class "Default")
      (node (ref "C1") (pin "-") (pinfunction "-_-") (pintype "passive"))
      (node (ref "R89") (pin "2") (pinfunction "2_2") (pintype "passive"))
    )
    (net (code "48") (name "Net-(LED1-PadA)") (class "Default")
      (node (ref "LED1") (pin "A") (pinfunction "A_A") (pintype "passive"))
      (node (ref "R1") (pin "1") (pinfunction "1_1") (pintype "passive"))
    )
    (net (code "49") (name "Net-(LED2-PadA)") (class "Default")
      (node (ref "LED2") (pin "A") (pinfunction "A_A") (pintype "passive"))
      (node (ref "R2") (pin "1") (pinfunction "1_1") (pintype "passive"))
    )
    (net (code "50") (name "Net-(LED3-PadA)") (class "Default")
      (node (ref "LED3") (pin "A") (pinfunction "A_A") (pintype "passive"))
      (node (ref "R3") (pin "1") (pinfunction "1_1") (pintype "passive"))
    )
    (net (code "51") (name "Net-(LED4-PadA)") (class "Default")
      (node (ref "LED4") (pin "A") (pinfunction "A_A") (pintype "passive"))
      (node (ref "R4") (pin "1") (pinfunction "1_1") (pintype "passive"))
    )
    (net (code "52") (name "Net-(LED9-PadA)") (class "Default")
      (node (ref "LED9") (pin "A") (pinfunction "A_A") (pintype "passive"))
      (node (ref "R17") (pin "1") (pinfunction "1_1") (pintype "passive"))
    )
    (net (code "53") (name "Net-(LED10-PadA)") (class "Default")
      (node (ref "LED10") (pin "A") (pinfunction "A_A") (pintype "passive"))
      (node (ref "R18") (pin "1") (pinfunction "1_1") (pintype "passive"))
    )
    (net (code "54") (name "Net-(LED11-PadA)") (class "Default")
      (node (ref "LED11") (pin "A") (pinfunction "A_A") (pintype "passive"))
      (node (ref "R19") (pin "1") (pinfunction "1_1") (pintype "passive"))
    )
    (net (code "55") (name "Net-(LED12-PadA)") (class "Default")
      (node (ref "LED12") (pin "A") (pinfunction "A_A") (pintype "passive"))
      (node (ref "R20") (pin "1") (pinfunction "1_1") (pintype "passive"))
    )
    (net (code "56") (name "Net-(LED13-PadA)") (class "Default")
      (node (ref "LED13") (pin "A") (pinfunction "A_A") (pintype "passive"))
      (node (ref "R21") (pin "1") (pinfunction "1_1") (pintype "passive"))
    )
    (net (code "57") (name "Net-(LED14-PadA)") (class "Default")
      (node (ref "LED14") (pin "A") (pinfunction "A_A") (pintype "passive"))
      (node (ref "R22") (pin "1") (pinfunction "1_1") (pintype "passive"))
    )
    (net (code "58") (name "Net-(LED15-PadA)") (class "Default")
      (node (ref "LED15") (pin "A") (pinfunction "A_A") (pintype "passive"))
      (node (ref "R23") (pin "1") (pinfunction "1_1") (pintype "passive"))
    )
    (net (code "59") (name "Net-(LED16-PadA)") (class "Default")
      (node (ref "LED16") (pin "A") (pinfunction "A_A") (pintype "passive"))
      (node (ref "R24") (pin "1") (pinfunction "1_1") (pintype "passive"))
    )
    (net (code "60") (name "Net-(LED17-PadA)") (class "Default")
      (node (ref "LED17") (pin "A") (pinfunction "A_A") (pintype "passive"))
      (node (ref "R33") (pin "1") (pinfunction "1_1") (pintype "passive"))
    )
    (net (code "61") (name "Net-(LED18-PadA)") (class "Default")
      (node (ref "LED18") (pin "A") (pinfunction "A_A") (pintype "passive"))
      (node (ref "R34") (pin "1") (pinfunction "1_1") (pintype "passive"))
    )
    (net (code "62") (name "Net-(LED19-PadA)") (class "Default")
      (node (ref "LED19") (pin "A") (pinfunction "A_A") (pintype "passive"))
      (node (ref "R35") (pin "1") (pinfunction "1_1") (pintype "passive"))
    )
    (net (code "63") (name "Net-(LED20-PadA)") (class "Default")
      (node (ref "LED20") (pin "A") (pinfunction "A_A") (pintype "passive"))
      (node (ref "R36") (pin "1") (pinfunction "1_1") (pintype "passive"))
    )
    (net (code "64") (name "Net-(LED21-PadA)") (class "Default")
      (node (ref "LED21") (pin "A") (pinfunction "A_A") (pintype "passive"))
      (node (ref "R37") (pin "1") (pinfunction "1_1") (pintype "passive"))
    )
    (net (code "65") (name "Net-(LED22-PadA)") (class "Default")
      (node (ref "LED22") (pin "A") (pinfunction "A_A") (pintype "passive"))
      (node (ref "R38") (pin "1") (pinfunction "1_1") (pintype "passive"))
    )
    (net (code "66") (name "Net-(LED23-PadA)") (class "Default")
      (node (ref "LED23") (pin "A") (pinfunction "A_A") (pintype "passive"))
      (node (ref "R39") (pin "1") (pinfunction "1_1") (pintype "passive"))
    )
    (net (code "67") (name "Net-(LED24-PadA)") (class "Default")
      (node (ref "LED24") (pin "A") (pinfunction "A_A") (pintype "passive"))
      (node (ref "R40") (pin "1") (pinfunction "1_1") (pintype "passive"))
    )
    (net (code "68") (name "Net-(LED25-PadA)") (class "Default")
      (node (ref "LED25") (pin "A") (pinfunction "A_A") (pintype "passive"))
      (node (ref "R49") (pin "1") (pinfunction "1_1") (pintype "passive"))
    )
    (net (code "69") (name "Net-(LED26-PadA)") (class "Default")
      (node (ref "LED26") (pin "A") (pinfunction "A_A") (pintype "passive"))
      (node (ref "R50") (pin "1") (pinfunction "1_1") (pintype "passive"))
    )
    (net (code "70") (name "Net-(LED27-PadA)") (class "Default")
      (node (ref "LED27") (pin "A") (pinfunction "A_A") (pintype "passive"))
      (node (ref "R51") (pin "1") (pinfunction "1_1") (pintype "passive"))
    )
    (net (code "71") (name "Net-(LED28-PadA)") (class "Default")
      (node (ref "LED28") (pin "A") (pinfunction "A_A") (pintype "passive"))
      (node (ref "R52") (pin "1") (pinfunction "1_1") (pintype "passive"))
    )
    (net (code "72") (name "Net-(LED29-PadA)") (class "Default")
      (node (ref "LED29") (pin "A") (pinfunction "A_A") (pintype "passive"))
      (node (ref "R53") (pin "1") (pinfunction "1_1") (pintype "passive"))
    )
    (net (code "73") (name "Net-(LED30-PadA)") (class "Default")
      (node (ref "LED30") (pin "A") (pinfunction "A_A") (pintype "passive"))
      (node (ref "R54") (pin "1") (pinfunction "1_1") (pintype "passive"))
    )
    (net (code "74") (name "Net-(LED31-PadA)") (class "Default")
      (node (ref "LED31") (pin "A") (pinfunction "A_A") (pintype "passive"))
      (node (ref "R55") (pin "1") (pinfunction "1_1") (pintype "passive"))
    )
    (net (code "75") (name "Net-(LED32-PadA)") (class "Default")
      (node (ref "LED32") (pin "A") (pinfunction "A_A") (pintype "passive"))
      (node (ref "R56") (pin "1") (pinfunction "1_1") (pintype "passive"))
    )
    (net (code "76") (name "Net-(LED33-PadA)") (class "Default")
      (node (ref "LED33") (pin "A") (pinfunction "A_A") (pintype "passive"))
      (node (ref "R65") (pin "1") (pinfunction "1_1") (pintype "passive"))
    )
    (net (code "77") (name "Net-(LED34-PadA)") (class "Default")
      (node (ref "LED34") (pin "A") (pinfunction "A_A") (pintype "passive"))
      (node (ref "R66") (pin "1") (pinfunction "1_1") (pintype "passive"))
    )
    (net (code "78") (name "Net-(LED35-PadA)") (class "Default")
      (node (ref "LED35") (pin "A") (pinfunction "A_A") (pintype "passive"))
      (node (ref "R67") (pin "1") (pinfunction "1_1") (pintype "passive"))
    )
    (net (code "79") (name "Net-(LED36-PadA)") (class "Default")
      (node (ref "LED36") (pin "A") (pinfunction "A_A") (pintype "passive"))
      (node (ref "R68") (pin "1") (pinfunction "1_1") (pintype "passive"))
    )
    (net (code "80") (name "Net-(LED37-PadA)") (class "Default")
      (node (ref "LED37") (pin "A") (pinfunction "A_A") (pintype "passive"))
      (node (ref "R69") (pin "1") (pinfunction "1_1") (pintype "passive"))
    )
    (net (code "81") (name "Net-(LED38-PadA)") (class "Default")
      (node (ref "LED38") (pin "A") (pinfunction "A_A") (pintype "passive"))
      (node (ref "R70") (pin "1") (pinfunction "1_1") (pintype "passive"))
    )
    (net (code "82") (name "Net-(LED39-PadA)") (class "Default")
      (node (ref "LED39") (pin "A") (pinfunction "A_A") (pintype "passive"))
      (node (ref "R71") (pin "1") (pinfunction "1_1") (pintype "passive"))
    )
    (net (code "83") (name "Net-(LED40-PadA)") (class "Default")
      (node (ref "LED40") (pin "A") (pinfunction "A_A") (pintype "passive"))
      (node (ref "R72") (pin "1") (pinfunction "1_1") (pintype "passive"))
    )
    (net (code "84") (name "Net-(U1-1B)") (class "Default")
      (node (ref "R25") (pin "2") (pinfunction "2_2") (pintype "passive"))
      (node (ref "U1") (pin "1") (pinfunction "1B_1") (pintype "input"))
    )
    (net (code "85") (name "Net-(U1-1C)") (class "Default")
      (node (ref "LED9") (pin "C") (pinfunction "C_C") (pintype "passive"))
      (node (ref "U1") (pin "18") (pinfunction "1C_18") (pintype "output"))
    )
    (net (code "86") (name "Net-(U1-2B)") (class "Default")
      (node (ref "R26") (pin "2") (pinfunction "2_2") (pintype "passive"))
      (node (ref "U1") (pin "2") (pinfunction "2B_2") (pintype "input"))
    )
    (net (code "87") (name "Net-(U1-2C)") (class "Default")
      (node (ref "LED10") (pin "C") (pinfunction "C_C") (pintype "passive"))
      (node (ref "U1") (pin "17") (pinfunction "2C_17") (pintype "output"))
    )
    (net (code "88") (name "Net-(U1-3B)") (class "Default")
      (node (ref "R27") (pin "2") (pinfunction "2_2") (pintype "passive"))
      (node (ref "U1") (pin "3") (pinfunction "3B_3") (pintype "input"))
    )
    (net (code "89") (name "Net-(U1-3C)") (class "Default")
      (node (ref "LED11") (pin "C") (pinfunction "C_C") (pintype "passive"))
      (node (ref "U1") (pin "16") (pinfunction "3C_16") (pintype "output"))
    )
    (net (code "90") (name "Net-(U1-4B)") (class "Default")
      (node (ref "R28") (pin "2") (pinfunction "2_2") (pintype "passive"))
      (node (ref "U1") (pin "4") (pinfunction "4B_4") (pintype "input"))
    )
    (net (code "91") (name "Net-(U1-4C)") (class "Default")
      (node (ref "LED12") (pin "C") (pinfunction "C_C") (pintype "passive"))
      (node (ref "U1") (pin "15") (pinfunction "4C_15") (pintype "output"))
    )
    (net (code "92") (name "Net-(U1-5B)") (class "Default")
      (node (ref "R29") (pin "2") (pinfunction "2_2") (pintype "passive"))
      (node (ref "U1") (pin "5") (pinfunction "5B_5") (pintype "input"))
    )
    (net (code "93") (name "Net-(U1-5C)") (class "Default")
      (node (ref "LED13") (pin "C") (pinfunction "C_C") (pintype "passive"))
      (node (ref "U1") (pin "14") (pinfunction "5C_14") (pintype "output"))
    )
    (net (code "94") (name "Net-(U1-6B)") (class "Default")
      (node (ref "R30") (pin "2") (pinfunction "2_2") (pintype "passive"))
      (node (ref "U1") (pin "6") (pinfunction "6B_6") (pintype "input"))
    )
    (net (code "95") (name "Net-(U1-6C)") (class "Default")
      (node (ref "LED14") (pin "C") (pinfunction "C_C") (pintype "passive"))
      (node (ref "U1") (pin "13") (pinfunction "6C_13") (pintype "output"))
    )
    (net (code "96") (name "Net-(U1-7B)") (class "Default")
      (node (ref "R31") (pin "2") (pinfunction "2_2") (pintype "passive"))
      (node (ref "U1") (pin "7") (pinfunction "7B_7") (pintype "input"))
    )
    (net (code "97") (name "Net-(U1-7C)") (class "Default")
      (node (ref "LED15") (pin "C") (pinfunction "C_C") (pintype "passive"))
      (node (ref "U1") (pin "12") (pinfunction "7C_12") (pintype "output"))
    )
    (net (code "98") (name "Net-(U1-8B)") (class "Default")
      (node (ref "R32") (pin "2") (pinfunction "2_2") (pintype "passive"))
      (node (ref "U1") (pin "8") (pinfunction "8B_8") (pintype "input"))
    )
    (net (code "99") (name "Net-(U1-8C)") (class "Default")
      (node (ref "LED16") (pin "C") (pinfunction "C_C") (pintype "passive"))
      (node (ref "U1") (pin "11") (pinfunction "8C_11") (pintype "output"))
    )
    (net (code "100") (name "Net-(U2-1B)") (class "Default")
      (node (ref "R9") (pin "2") (pinfunction "2_2") (pintype "passive"))
      (node (ref "U2") (pin "1") (pinfunction "1B_1") (pintype "input"))
    )
    (net (code "101") (name "Net-(U2-1C)") (class "Default")
      (node (ref "LED1") (pin "C") (pinfunction "C_C") (pintype "passive"))
      (node (ref "U2") (pin "18") (pinfunction "1C_18") (pintype "output"))
    )
    (net (code "102") (name "Net-(U2-2B)") (class "Default")
      (node (ref "R10") (pin "2") (pinfunction "2_2") (pintype "passive"))
      (node (ref "U2") (pin "2") (pinfunction "2B_2") (pintype "input"))
    )
    (net (code "103") (name "Net-(U2-2C)") (class "Default")
      (node (ref "LED2") (pin "C") (pinfunction "C_C") (pintype "passive"))
      (node (ref "U2") (pin "17") (pinfunction "2C_17") (pintype "output"))
    )
    (net (code "104") (name "Net-(U2-3B)") (class "Default")
      (node (ref "R11") (pin "2") (pinfunction "2_2") (pintype "passive"))
      (node (ref "U2") (pin "3") (pinfunction "3B_3") (pintype "input"))
    )
    (net (code "105") (name "Net-(U2-3C)") (class "Default")
      (node (ref "LED3") (pin "C") (pinfunction "C_C") (pintype "passive"))
      (node (ref "U2") (pin "16") (pinfunction "3C_16") (pintype "output"))
    )
    (net (code "106") (name "Net-(U2-4B)") (class "Default")
      (node (ref "R12") (pin "2") (pinfunction "2_2") (pintype "passive"))
      (node (ref "U2") (pin "4") (pinfunction "4B_4") (pintype "input"))
    )
    (net (code "107") (name "Net-(U2-4C)") (class "Default")
      (node (ref "LED4") (pin "C") (pinfunction "C_C") (pintype "passive"))
      (node (ref "U2") (pin "15") (pinfunction "4C_15") (pintype "output"))
    )
    (net (code "108") (name "Net-(U3-1B)") (class "Default")
      (node (ref "R41") (pin "2") (pinfunction "2_2") (pintype "passive"))
      (node (ref "U3") (pin "1") (pinfunction "1B_1") (pintype "input"))
    )
    (net (code "109") (name "Net-(U3-1C)") (class "Default")
      (node (ref "LED17") (pin "C") (pinfunction "C_C") (pintype "passive"))
      (node (ref "U3") (pin "18") (pinfunction "1C_18") (pintype "output"))
    )
    (net (code "110") (name "Net-(U3-2B)") (class "Default")
      (node (ref "R42") (pin "2") (pinfunction "2_2") (pintype "passive"))
      (node (ref "U3") (pin "2") (pinfunction "2B_2") (pintype "input"))
    )
    (net (code "111") (name "Net-(U3-2C)") (class "Default")
      (node (ref "LED18") (pin "C") (pinfunction "C_C") (pintype "passive"))
      (node (ref "U3") (pin "17") (pinfunction "2C_17") (pintype "output"))
    )
    (net (code "112") (name "Net-(U3-3B)") (class "Default")
      (node (ref "R43") (pin "2") (pinfunction "2_2") (pintype "passive"))
      (node (ref "U3") (pin "3") (pinfunction "3B_3") (pintype "input"))
    )
    (net (code "113") (name "Net-(U3-3C)") (class "Default")
      (node (ref "LED19") (pin "C") (pinfunction "C_C") (pintype "passive"))
      (node (ref "U3") (pin "16") (pinfunction "3C_16") (pintype "output"))
    )
    (net (code "114") (name "Net-(U3-4B)") (class "Default")
      (node (ref "R44") (pin "2") (pinfunction "2_2") (pintype "passive"))
      (node (ref "U3") (pin "4") (pinfunction "4B_4") (pintype "input"))
    )
    (net (code "115") (name "Net-(U3-4C)") (class "Default")
      (node (ref "LED20") (pin "C") (pinfunction "C_C") (pintype "passive"))
      (node (ref "U3") (pin "15") (pinfunction "4C_15") (pintype "output"))
    )
    (net (code "116") (name "Net-(U3-5B)") (class "Default")
      (node (ref "R45") (pin "2") (pinfunction "2_2") (pintype "passive"))
      (node (ref "U3") (pin "5") (pinfunction "5B_5") (pintype "input"))
    )
    (net (code "117") (name "Net-(U3-5C)") (class "Default")
      (node (ref "LED21") (pin "C") (pinfunction "C_C") (pintype "passive"))
      (node (ref "U3") (pin "14") (pinfunction "5C_14") (pintype "output"))
    )
    (net (code "118") (name "Net-(U3-6B)") (class "Default")
      (node (ref "R46") (pin "2") (pinfunction "2_2") (pintype "passive"))
      (node (ref "U3") (pin "6") (pinfunction "6B_6") (pintype "input"))
    )
    (net (code "119") (name "Net-(U3-6C)") (class "Default")
      (node (ref "LED22") (pin "C") (pinfunction "C_C") (pintype "passive"))
      (node (ref "U3") (pin "13") (pinfunction "6C_13") (pintype "output"))
    )
    (net (code "120") (name "Net-(U3-7B)") (class "Default")
      (node (ref "R47") (pin "2") (pinfunction "2_2") (pintype "passive"))
      (node (ref "U3") (pin "7") (pinfunction "7B_7") (pintype "input"))
    )
    (net (code "121") (name "Net-(U3-7C)") (class "Default")
      (node (ref "LED23") (pin "C") (pinfunction "C_C") (pintype "passive"))
      (node (ref "U3") (pin "12") (pinfunction "7C_12") (pintype "output"))
    )
    (net (code "122") (name "Net-(U3-8B)") (class "Default")
      (node (ref "R48") (pin "2") (pinfunction "2_2") (pintype "passive"))
      (node (ref "U3") (pin "8") (pinfunction "8B_8") (pintype "input"))
    )
    (net (code "123") (name "Net-(U3-8C)") (class "Default")
      (node (ref "LED24") (pin "C") (pinfunction "C_C") (pintype "passive"))
      (node (ref "U3") (pin "11") (pinfunction "8C_11") (pintype "output"))
    )
    (net (code "124") (name "Net-(U4-1B)") (class "Default")
      (node (ref "R57") (pin "2") (pinfunction "2_2") (pintype "passive"))
      (node (ref "U4") (pin "1") (pinfunction "1B_1") (pintype "input"))
    )
    (net (code "125") (name "Net-(U4-1C)") (class "Default")
      (node (ref "LED25") (pin "C") (pinfunction "C_C") (pintype "passive"))
      (node (ref "U4") (pin "18") (pinfunction "1C_18") (pintype "output"))
    )
    (net (code "126") (name "Net-(U4-2B)") (class "Default")
      (node (ref "R58") (pin "2") (pinfunction "2_2") (pintype "passive"))
      (node (ref "U4") (pin "2") (pinfunction "2B_2") (pintype "input"))
    )
    (net (code "127") (name "Net-(U4-2C)") (class "Default")
      (node (ref "LED26") (pin "C") (pinfunction "C_C") (pintype "passive"))
      (node (ref "U4") (pin "17") (pinfunction "2C_17") (pintype "output"))
    )
    (net (code "128") (name "Net-(U4-3B)") (class "Default")
      (node (ref "R59") (pin "2") (pinfunction "2_2") (pintype "passive"))
      (node (ref "U4") (pin "3") (pinfunction "3B_3") (pintype "input"))
    )
    (net (code "129") (name "Net-(U4-3C)") (class "Default")
      (node (ref "LED27") (pin "C") (pinfunction "C_C") (pintype "passive"))
      (node (ref "U4") (pin "16") (pinfunction "3C_16") (pintype "output"))
    )
    (net (code "130") (name "Net-(U4-4B)") (class "Default")
      (node (ref "R60") (pin "2") (pinfunction "2_2") (pintype "passive"))
      (node (ref "U4") (pin "4") (pinfunction "4B_4") (pintype "input"))
    )
    (net (code "131") (name "Net-(U4-4C)") (class "Default")
      (node (ref "LED28") (pin "C") (pinfunction "C_C") (pintype "passive"))
      (node (ref "U4") (pin "15") (pinfunction "4C_15") (pintype "output"))
    )
    (net (code "132") (name "Net-(U4-5B)") (class "Default")
      (node (ref "R61") (pin "2") (pinfunction "2_2") (pintype "passive"))
      (node (ref "U4") (pin "5") (pinfunction "5B_5") (pintype "input"))
    )
    (net (code "133") (name "Net-(U4-5C)") (class "Default")
      (node (ref "LED29") (pin "C") (pinfunction "C_C") (pintype "passive"))
      (node (ref "U4") (pin "14") (pinfunction "5C_14") (pintype "output"))
    )
    (net (code "134") (name "Net-(U4-6B)") (class "Default")
      (node (ref "R62") (pin "2") (pinfunction "2_2") (pintype "passive"))
      (node (ref "U4") (pin "6") (pinfunction "6B_6") (pintype "input"))
    )
    (net (code "135") (name "Net-(U4-6C)") (class "Default")
      (node (ref "LED30") (pin "C") (pinfunction "C_C") (pintype "passive"))
      (node (ref "U4") (pin "13") (pinfunction "6C_13") (pintype "output"))
    )
    (net (code "136") (name "Net-(U4-7B)") (class "Default")
      (node (ref "R63") (pin "2") (pinfunction "2_2") (pintype "passive"))
      (node (ref "U4") (pin "7") (pinfunction "7B_7") (pintype "input"))
    )
    (net (code "137") (name "Net-(U4-7C)") (class "Default")
      (node (ref "LED31") (pin "C") (pinfunction "C_C") (pintype "passive"))
      (node (ref "U4") (pin "12") (pinfunction "7C_12") (pintype "output"))
    )
    (net (code "138") (name "Net-(U4-8B)") (class "Default")
      (node (ref "R64") (pin "2") (pinfunction "2_2") (pintype "passive"))
      (node (ref "U4") (pin "8") (pinfunction "8B_8") (pintype "input"))
    )
    (net (code "139") (name "Net-(U4-8C)") (class "Default")
      (node (ref "LED32") (pin "C") (pinfunction "C_C") (pintype "passive"))
      (node (ref "U4") (pin "11") (pinfunction "8C_11") (pintype "output"))
    )
    (net (code "140") (name "Net-(U5-1B)") (class "Default")
      (node (ref "R73") (pin "2") (pinfunction "2_2") (pintype "passive"))
      (node (ref "U5") (pin "1") (pinfunction "1B_1") (pintype "input"))
    )
    (net (code "141") (name "Net-(U5-1C)") (class "Default")
      (node (ref "LED33") (pin "C") (pinfunction "C_C") (pintype "passive"))
      (node (ref "U5") (pin "18") (pinfunction "1C_18") (pintype "output"))
    )
    (net (code "142") (name "Net-(U5-2B)") (class "Default")
      (node (ref "R74") (pin "2") (pinfunction "2_2") (pintype "passive"))
      (node (ref "U5") (pin "2") (pinfunction "2B_2") (pintype "input"))
    )
    (net (code "143") (name "Net-(U5-2C)") (class "Default")
      (node (ref "LED34") (pin "C") (pinfunction "C_C") (pintype "passive"))
      (node (ref "U5") (pin "17") (pinfunction "2C_17") (pintype "output"))
    )
    (net (code "144") (name "Net-(U5-3B)") (class "Default")
      (node (ref "R75") (pin "2") (pinfunction "2_2") (pintype "passive"))
      (node (ref "U5") (pin "3") (pinfunction "3B_3") (pintype "input"))
    )
    (net (code "145") (name "Net-(U5-3C)") (class "Default")
      (node (ref "LED35") (pin "C") (pinfunction "C_C") (pintype "passive"))
      (node (ref "U5") (pin "16") (pinfunction "3C_16") (pintype "output"))
    )
    (net (code "146") (name "Net-(U5-4B)") (class "Default")
      (node (ref "R76") (pin "2") (pinfunction "2_2") (pintype "passive"))
      (node (ref "U5") (pin "4") (pinfunction "4B_4") (pintype "input"))
    )
    (net (code "147") (name "Net-(U5-4C)") (class "Default")
      (node (ref "LED36") (pin "C") (pinfunction "C_C") (pintype "passive"))
      (node (ref "U5") (pin "15") (pinfunction "4C_15") (pintype "output"))
    )
    (net (code "148") (name "Net-(U5-5B)") (class "Default")
      (node (ref "R77") (pin "2") (pinfunction "2_2") (pintype "passive"))
      (node (ref "U5") (pin "5") (pinfunction "5B_5") (pintype "input"))
    )
    (net (code "149") (name "Net-(U5-5C)") (class "Default")
      (node (ref "LED37") (pin "C") (pinfunction "C_C") (pintype "passive"))
      (node (ref "U5") (pin "14") (pinfunction "5C_14") (pintype "output"))
    )
    (net (code "150") (name "Net-(U5-6B)") (class "Default")
      (node (ref "R78") (pin "2") (pinfunction "2_2") (pintype "passive"))
      (node (ref "U5") (pin "6") (pinfunction "6B_6") (pintype "input"))
    )
    (net (code "151") (name "Net-(U5-6C)") (class "Default")
      (node (ref "LED38") (pin "C") (pinfunction "C_C") (pintype "passive"))
      (node (ref "U5") (pin "13") (pinfunction "6C_13") (pintype "output"))
    )
    (net (code "152") (name "Net-(U5-7B)") (class "Default")
      (node (ref "R79") (pin "2") (pinfunction "2_2") (pintype "passive"))
      (node (ref "U5") (pin "7") (pinfunction "7B_7") (pintype "input"))
    )
    (net (code "153") (name "Net-(U5-7C)") (class "Default")
      (node (ref "LED39") (pin "C") (pinfunction "C_C") (pintype "passive"))
      (node (ref "U5") (pin "12") (pinfunction "7C_12") (pintype "output"))
    )
    (net (code "154") (name "Net-(U5-8B)") (class "Default")
      (node (ref "R80") (pin "2") (pinfunction "2_2") (pintype "passive"))
      (node (ref "U5") (pin "8") (pinfunction "8B_8") (pintype "input"))
    )
    (net (code "155") (name "Net-(U5-8C)") (class "Default")
      (node (ref "LED40") (pin "C") (pinfunction "C_C") (pintype "passive"))
      (node (ref "U5") (pin "11") (pinfunction "8C_11") (pintype "output"))
    )
    (net (code "156") (name "OUT") (class "Default")
      (node (ref "PCB2") (pin "6") (pinfunction "6_6") (pintype "bidirectional"))
      (node (ref "R77") (pin "1") (pinfunction "1_1") (pintype "passive"))
    )
    (net (code "157") (name "PROT") (class "Default")
      (node (ref "PCB2") (pin "13") (pinfunction "13_13") (pintype "bidirectional"))
      (node (ref "R9") (pin "1") (pinfunction "1_1") (pintype "passive"))
    )
    (net (code "158") (name "PROTECT") (class "Default")
      (node (ref "PCB2") (pin "A6") (pinfunction "A6_A6") (pintype "bidirectional"))
      (node (ref "S3") (pin "P1") (pinfunction "P1_P1") (pintype "bidirectional"))
    )
    (net (code "159") (name "RESET") (class "Default")
      (node (ref "PCB2") (pin "52") (pinfunction "52_52") (pintype "bidirectional"))
      (node (ref "S4") (pin "P1") (pinfunction "P1_P1") (pintype "bidirectional"))
    )
    (net (code "160") (name "RUN") (class "Default")
      (node (ref "PCB2") (pin "20") (pinfunction "20(SDA)_20") (pintype "bidirectional"))
      (node (ref "S8") (pin "P3") (pinfunction "P3_P3") (pintype "bidirectional"))
    )
    (net (code "161") (name "SERIAL_RX") (class "Default")
      (node (ref "PCB2") (pin "19") (pinfunction "19(RX1)_19") (pintype "bidirectional"))
    )
    (net (code "162") (name "SERIAL_TX") (class "Default")
      (node (ref "PCB2") (pin "18") (pinfunction "18(TX1)_18") (pintype "bidirectional"))
    )
    (net (code "163") (name "SLOW") (class "Default")
      (node (ref "PCB2") (pin "A1") (pinfunction "A1_A1") (pintype "bidirectional"))
      (node (ref "S7") (pin "P3") (pinfunction "P3_P3") (pintype "bidirectional"))
    )
    (net (code "164") (name "STACK") (class "Default")
      (node (ref "PCB2") (pin "4") (pinfunction "4_4") (pintype "bidirectional"))
      (node (ref "R75") (pin "1") (pinfunction "1_1") (pintype "passive"))
    )
    (net (code "165") (name "STEP") (class "Default")
      (node (ref "PCB2") (pin "A0") (pinfunction "A0_A0") (pintype "bidirectional"))
      (node (ref "S7") (pin "P1") (pinfunction "P1_P1") (pintype "bidirectional"))
    )
    (net (code "166") (name "STOP") (class "Default")
      (node (ref "PCB2") (pin "21") (pinfunction "21(SCL)_21") (pintype "bidirectional"))
      (node (ref "S8") (pin "P1") (pinfunction "P1_P1") (pintype "bidirectional"))
    )
    (net (code "167") (name "SW0") (class "Default")
      (node (ref "PCB2") (pin "A8") (pinfunction "A8_A8") (pintype "bidirectional"))
      (node (ref "R88") (pin "1") (pinfunction "1_1") (pintype "passive"))
      (node (ref "S14") (pin "4") (pinfunction "4_4") (pintype "passive"))
    )
    (net (code "168") (name "SW1") (class "Default")
      (node (ref "PCB2") (pin "A9") (pinfunction "A9_A9") (pintype "bidirectional"))
      (node (ref "R87") (pin "1") (pinfunction "1_1") (pintype "passive"))
      (node (ref "S14") (pin "5") (pinfunction "5_5") (pintype "passive"))
    )
    (net (code "169") (name "SW2") (class "Default")
      (node (ref "PCB2") (pin "A10") (pinfunction "A10_A10") (pintype "bidirectional"))
      (node (ref "R86") (pin "1") (pinfunction "1_1") (pintype "passive"))
      (node (ref "S14") (pin "6") (pinfunction "6_6") (pintype "passive"))
    )
    (net (code "170") (name "SW3") (class "Default")
      (node (ref "PCB2") (pin "A11") (pinfunction "A11_A11") (pintype "bidirectional"))
      (node (ref "R85") (pin "1") (pinfunction "1_1") (pintype "passive"))
      (node (ref "S13") (pin "4") (pinfunction "4_4") (pintype "passive"))
    )
    (net (code "171") (name "SW4") (class "Default")
      (node (ref "PCB2") (pin "A12") (pinfunction "A12_A12") (pintype "bidirectional"))
      (node (ref "R84") (pin "1") (pinfunction "1_1") (pintype "passive"))
      (node (ref "S13") (pin "5") (pinfunction "5_5") (pintype "passive"))
    )
    (net (code "172") (name "SW5") (class "Default")
      (node (ref "PCB2") (pin "A13") (pinfunction "A13_A13") (pintype "bidirectional"))
      (node (ref "R83") (pin "1") (pinfunction "1_1") (pintype "passive"))
      (node (ref "S13") (pin "6") (pinfunction "6_6") (pintype "passive"))
    )
    (net (code "173") (name "SW6") (class "Default")
      (node (ref "PCB2") (pin "A14") (pinfunction "A14_A14") (pintype "bidirectional"))
      (node (ref "R82") (pin "1") (pinfunction "1_1") (pintype "passive"))
      (node (ref "S12") (pin "4") (pinfunction "4_4") (pintype "passive"))
    )
    (net (code "174") (name "SW7") (class "Default")
      (node (ref "PCB2") (pin "A15") (pinfunction "A15_A15") (pintype "bidirectional"))
      (node (ref "R81") (pin "1") (pinfunction "1_1") (pintype "passive"))
      (node (ref "S12") (pin "5") (pinfunction "5_5") (pintype "passive"))
    )
    (net (code "175") (name "SW8") (class "Default")
      (node (ref "PCB2") (pin "17") (pinfunction "17(RX2)_17") (pintype "bidirectional"))
      (node (ref "R16") (pin "1") (pinfunction "1_1") (pintype "passive"))
      (node (ref "S12") (pin "6") (pinfunction "6_6") (pintype "passive"))
    )
    (net (code "176") (name "SW9") (class "Default")
      (node (ref "PCB2") (pin "16") (pinfunction "16(TX2)_16") (pintype "bidirectional"))
      (node (ref "R15") (pin "1") (pinfunction "1_1") (pintype "passive"))
      (node (ref "S11") (pin "4") (pinfunction "4_4") (pintype "passive"))
    )
    (net (code "177") (name "SW10") (class "Default")
      (node (ref "PCB2") (pin "23") (pinfunction "23_23") (pintype "bidirectional"))
      (node (ref "R14") (pin "1") (pinfunction "1_1") (pintype "passive"))
      (node (ref "S11") (pin "5") (pinfunction "5_5") (pintype "passive"))
    )
    (net (code "178") (name "SW11") (class "Default")
      (node (ref "PCB2") (pin "24") (pinfunction "24_24") (pintype "bidirectional"))
      (node (ref "R13") (pin "1") (pinfunction "1_1") (pintype "passive"))
      (node (ref "S11") (pin "6") (pinfunction "6_6") (pintype "passive"))
    )
    (net (code "179") (name "SW12") (class "Default")
      (node (ref "PCB2") (pin "SDA1") (pinfunction "SDA1_SDA1") (pintype "bidirectional"))
      (node (ref "R7") (pin "1") (pinfunction "1_1") (pintype "passive"))
      (node (ref "S9") (pin "4") (pinfunction "4_4") (pintype "passive"))
    )
    (net (code "180") (name "SW13") (class "Default")
      (node (ref "PCB2") (pin "SCL1") (pinfunction "SCL1_SCL1") (pintype "bidirectional"))
      (node (ref "R6") (pin "1") (pinfunction "1_1") (pintype "passive"))
      (node (ref "S9") (pin "5") (pinfunction "5_5") (pintype "passive"))
    )
    (net (code "181") (name "SW14") (class "Default")
      (node (ref "PCB2") (pin "42") (pinfunction "42_42") (pintype "bidirectional"))
      (node (ref "R5") (pin "1") (pinfunction "1_1") (pintype "passive"))
      (node (ref "S9") (pin "6") (pinfunction "6_6") (pintype "passive"))
    )
    (net (code "182") (name "SW15") (class "Default")
      (node (ref "PCB2") (pin "43") (pinfunction "43_43") (pintype "bidirectional"))
      (node (ref "R8") (pin "1") (pinfunction "1_1") (pintype "passive"))
      (node (ref "S10") (pin "2") (pinfunction "2_2") (pintype "passive"))
    )
    (net (code "183") (name "UNPROTECT") (class "Default")
      (node (ref "PCB2") (pin "A7") (pinfunction "A7_A7") (pintype "bidirectional"))
      (node (ref "S3") (pin "P3") (pinfunction "P3_P3") (pintype "bidirectional"))
    )
    (net (code "184") (name "VCC") (class "Default")
      (node (ref "R1") (pin "2") (pinfunction "2_2") (pintype "passive"))
      (node (ref "R13") (pin "2") (pinfunction "2_2") (pintype "passive"))
      (node (ref "R14") (pin "2") (pinfunction "2_2") (pintype "passive"))
      (node (ref "R15") (pin "2") (pinfunction "2_2") (pintype "passive"))
      (node (ref "R16") (pin "2") (pinfunction "2_2") (pintype "passive"))
      (node (ref "R17") (pin "2") (pinfunction "2_2") (pintype "passive"))
      (node (ref "R18") (pin "2") (pinfunction "2_2") (pintype "passive"))
      (node (ref "R19") (pin "2") (pinfunction "2_2") (pintype "passive"))
      (node (ref "R2") (pin "2") (pinfunction "2_2") (pintype "passive"))
      (node (ref "R20") (pin "2") (pinfunction "2_2") (pintype "passive"))
      (node (ref "R21") (pin "2") (pinfunction "2_2") (pintype "passive"))
      (node (ref "R22") (pin "2") (pinfunction "2_2") (pintype "passive"))
      (node (ref "R23") (pin "2") (pinfunction "2_2") (pintype "passive"))
      (node (ref "R24") (pin "2") (pinfunction "2_2") (pintype "passive"))
      (node (ref "R3") (pin "2") (pinfunction "2_2") (pintype "passive"))
      (node (ref "R33") (pin "2") (pinfunction "2_2") (pintype "passive"))
      (node (ref "R34") (pin "2") (pinfunction "2_2") (pintype "passive"))
      (node (ref "R35") (pin "2") (pinfunction "2_2") (pintype "passive"))
      (node (ref "R36") (pin "2") (pinfunction "2_2") (pintype "passive"))
      (node (ref "R37") (pin "2") (pinfunction "2_2") (pintype "passive"))
      (node (ref "R38") (pin "2") (pinfunction "2_2") (pintype "passive"))
      (node (ref "R39") (pin "2") (pinfunction "2_2") (pintype "passive"))
      (node (ref "R4") (pin "2") (pinfunction "2_2") (pintype "passive"))
      (node (ref "R40") (pin "2") (pinfunction "2_2") (pintype "passive"))
      (node (ref "R49") (pin "2") (pinfunction "2_2") (pintype "passive"))
      (node (ref "R5") (pin "2") (pinfunction "2_2") (pintype "passive"))
      (node (ref "R50") (pin "2") (pinfunction "2_2") (pintype "passive"))
      (node (ref "R51") (pin "2") (pinfunction "2_2") (pintype "passive"))
      (node (ref "R52") (pin "2") (pinfunction "2_2") (pintype "passive"))
      (node (ref "R53") (pin "2") (pinfunction "2_2") (pintype "passive"))
      (node (ref "R54") (pin "2") (pinfunction "2_2") (pintype "passive"))
      (node (ref "R55") (pin "2") (pinfunction "2_2") (pintype "passive"))
      (node (ref "R56") (pin "2") (pinfunction "2_2") (pintype "passive"))
      (node (ref "R6") (pin "2") (pinfunction "2_2") (pintype "passive"))
      (node (ref "R65") (pin "2") (pinfunction "2_2") (pintype "passive"))
      (node (ref "R66") (pin "2") (pinfunction "2_2") (pintype "passive"))
      (node (ref "R67") (pin "2") (pinfunction "2_2") (pintype "passive"))
      (node (ref "R68") (pin "2") (pinfunction "2_2") (pintype "passive"))
      (node (ref "R69") (pin "2") (pinfunction "2_2") (pintype "passive"))
      (node (ref "R7") (pin "2") (pinfunction "2_2") (pintype "passive"))
      (node (ref "R70") (pin "2") (pinfunction "2_2") (pintype "passive"))
      (node (ref "R71") (pin "2") (pinfunction "2_2") (pintype "passive"))
      (node (ref "R72") (pin "2") (pinfunction "2_2") (pintype "passive"))
      (node (ref "R8") (pin "2") (pinfunction "2_2") (pintype "passive"))
      (node (ref "R81") (pin "2") (pinfunction "2_2") (pintype "passive"))
      (node (ref "R82") (pin "2") (pinfunction "2_2") (pintype "passive"))
      (node (ref "R83") (pin "2") (pinfunction "2_2") (pintype "passive"))
      (node (ref "R84") (pin "2") (pinfunction "2_2") (pintype "passive"))
      (node (ref "R85") (pin "2") (pinfunction "2_2") (pintype "passive"))
      (node (ref "R86") (pin "2") (pinfunction "2_2") (pintype "passive"))
      (node (ref "R87") (pin "2") (pinfunction "2_2") (pintype "passive"))
      (node (ref "R88") (pin "2") (pinfunction "2_2") (pintype "passive"))
      (node (ref "U1") (pin "10") (pinfunction "COM_10") (pintype "output"))
      (node (ref "U2") (pin "10") (pinfunction "COM_10") (pintype "output"))
      (node (ref "U3") (pin "10") (pinfunction "COM_10") (pintype "output"))
      (node (ref "U4") (pin "10") (pinfunction "COM_10") (pintype "output"))
      (node (ref "U5") (pin "10") (pinfunction "COM_10") (pintype "output"))
    )
    (net (code "185") (name "VIN") (class "Default")
      (node (ref "CN1") (pin "PWR") (pinfunction "PWR_PWR") (pintype "power_in"))
      (node (ref "PCB2") (pin "VIN") (pinfunction "VIN_VIN") (pintype "bidirectional"))
    )
    (net (code "186") (name "WAIT") (class "Default")
      (node (ref "PCB2") (pin "10") (pinfunction "10_10") (pintype "bidirectional"))
      (node (ref "R12") (pin "1") (pinfunction "1_1") (pintype "passive"))
    )
    (net (code "187") (name "WO") (class "Default")
      (node (ref "PCB2") (pin "3") (pinfunction "3_3") (pintype "bidirectional"))
      (node (ref "R74") (pin "1") (pinfunction "1_1") (pintype "passive"))
    )
    (net (code "188") (name "unconnected-(J1-Pad1)") (class "Default")
      (node (ref "J1") (pin "1") (pinfunction "1_1") (pintype "passive"))
    )
    (net (code "189") (name "unconnected-(J1-Pad2)") (class "Default")
      (node (ref "J1") (pin "2") (pinfunction "2_2") (pintype "passive"))
    )
    (net (code "190") (name "unconnected-(J1-Pad3)") (class "Default")
      (node (ref "J1") (pin "3") (pinfunction "3_3") (pintype "passive"))
    )
    (net (code "191") (name "unconnected-(J1-Pad4)") (class "Default")
      (node (ref "J1") (pin "4") (pinfunction "4_4") (pintype "passive"))
    )
    (net (code "192") (name "unconnected-(J1-Pad5)") (class "Default")
      (node (ref "J1") (pin "5") (pinfunction "5_5") (pintype "passive"))
    )
    (net (code "193") (name "unconnected-(J1-Pad6)") (class "Default")
      (node (ref "J1") (pin "6") (pinfunction "6_6") (pintype "passive"))
    )
    (net (code "194") (name "unconnected-(J1-Pad7)") (class "Default")
      (node (ref "J1") (pin "7") (pinfunction "7_7") (pintype "passive"))
    )
    (net (code "195") (name "unconnected-(J1-Pad8)") (class "Default")
      (node (ref "J1") (pin "8") (pinfunction "8_8") (pintype "passive"))
    )
    (net (code "196") (name "unconnected-(J3-Pad1)") (class "Default")
      (node (ref "J3") (pin "1") (pinfunction "1_1") (pintype "passive"))
    )
    (net (code "197") (name "unconnected-(J3-Pad2)") (class "Default")
      (node (ref "J3") (pin "2") (pinfunction "2_2") (pintype "passive"))
    )
    (net (code "198") (name "unconnected-(J3-Pad3)") (class "Default")
      (node (ref "J3") (pin "3") (pinfunction "3_3") (pintype "passive"))
    )
    (net (code "199") (name "unconnected-(J3-Pad4)") (class "Default")
      (node (ref "J3") (pin "4") (pinfunction "4_4") (pintype "passive"))
    )
    (net (code "200") (name "unconnected-(J3-Pad5)") (class "Default")
      (node (ref "J3") (pin "5") (pinfunction "5_5") (pintype "passive"))
    )
    (net (code "201") (name "unconnected-(J3-Pad6)") (class "Default")
      (node (ref "J3") (pin "6") (pinfunction "6_6") (pintype "passive"))
    )
    (net (code "202") (name "unconnected-(PCB2-(N{slash}C)-PadN{slash}C)") (class "Default")
      (node (ref "PCB2") (pin "N/C") (pinfunction "(N/C)_N/C") (pintype "bidirectional"))
    )
    (net (code "203") (name "unconnected-(PCB2-0(RX)-Pad0)") (class "Default")
      (node (ref "PCB2") (pin "0") (pinfunction "0(RX)_0") (pintype "bidirectional"))
    )
    (net (code "204") (name "unconnected-(PCB2-1(TX)-Pad1)") (class "Default")
      (node (ref "PCB2") (pin "1") (pinfunction "1(TX)_1") (pintype "bidirectional"))
    )
    (net (code "205") (name "unconnected-(U2-5B-Pad5)") (class "Default")
      (node (ref "U2") (pin "5") (pinfunction "5B_5") (pintype "input"))
    )
    (net (code "206") (name "unconnected-(U2-5C-Pad14)") (class "Default")
      (node (ref "U2") (pin "14") (pinfunction "5C_14") (pintype "output"))
    )
    (net (code "207") (name "unconnected-(U2-6B-Pad6)") (class "Default")
      (node (ref "U2") (pin "6") (pinfunction "6B_6") (pintype "input"))
    )
    (net (code "208") (name "unconnected-(U2-6C-Pad13)") (class "Default")
      (node (ref "U2") (pin "13") (pinfunction "6C_13") (pintype "output"))
    )
    (net (code "209") (name "unconnected-(U2-7B-Pad7)") (class "Default")
      (node (ref "U2") (pin "7") (pinfunction "7B_7") (pintype "input"))
    )
    (net (code "210") (name "unconnected-(U2-7C-Pad12)") (class "Default")
      (node (ref "U2") (pin "12") (pinfunction "7C_12") (pintype "output"))
    )
    (net (code "211") (name "unconnected-(U2-8B-Pad8)") (class "Default")
      (node (ref "U2") (pin "8") (pinfunction "8B_8") (pintype "input"))
    )
    (net (code "212") (name "unconnected-(U2-8C-Pad11)") (class "Default")
      (node (ref "U2") (pin "11") (pinfunction "8C_11") (pintype "output"))
    )
  )
)
